# P2P_PROT_1.net
KiCad netlist of a schematic drawn in EAGLE
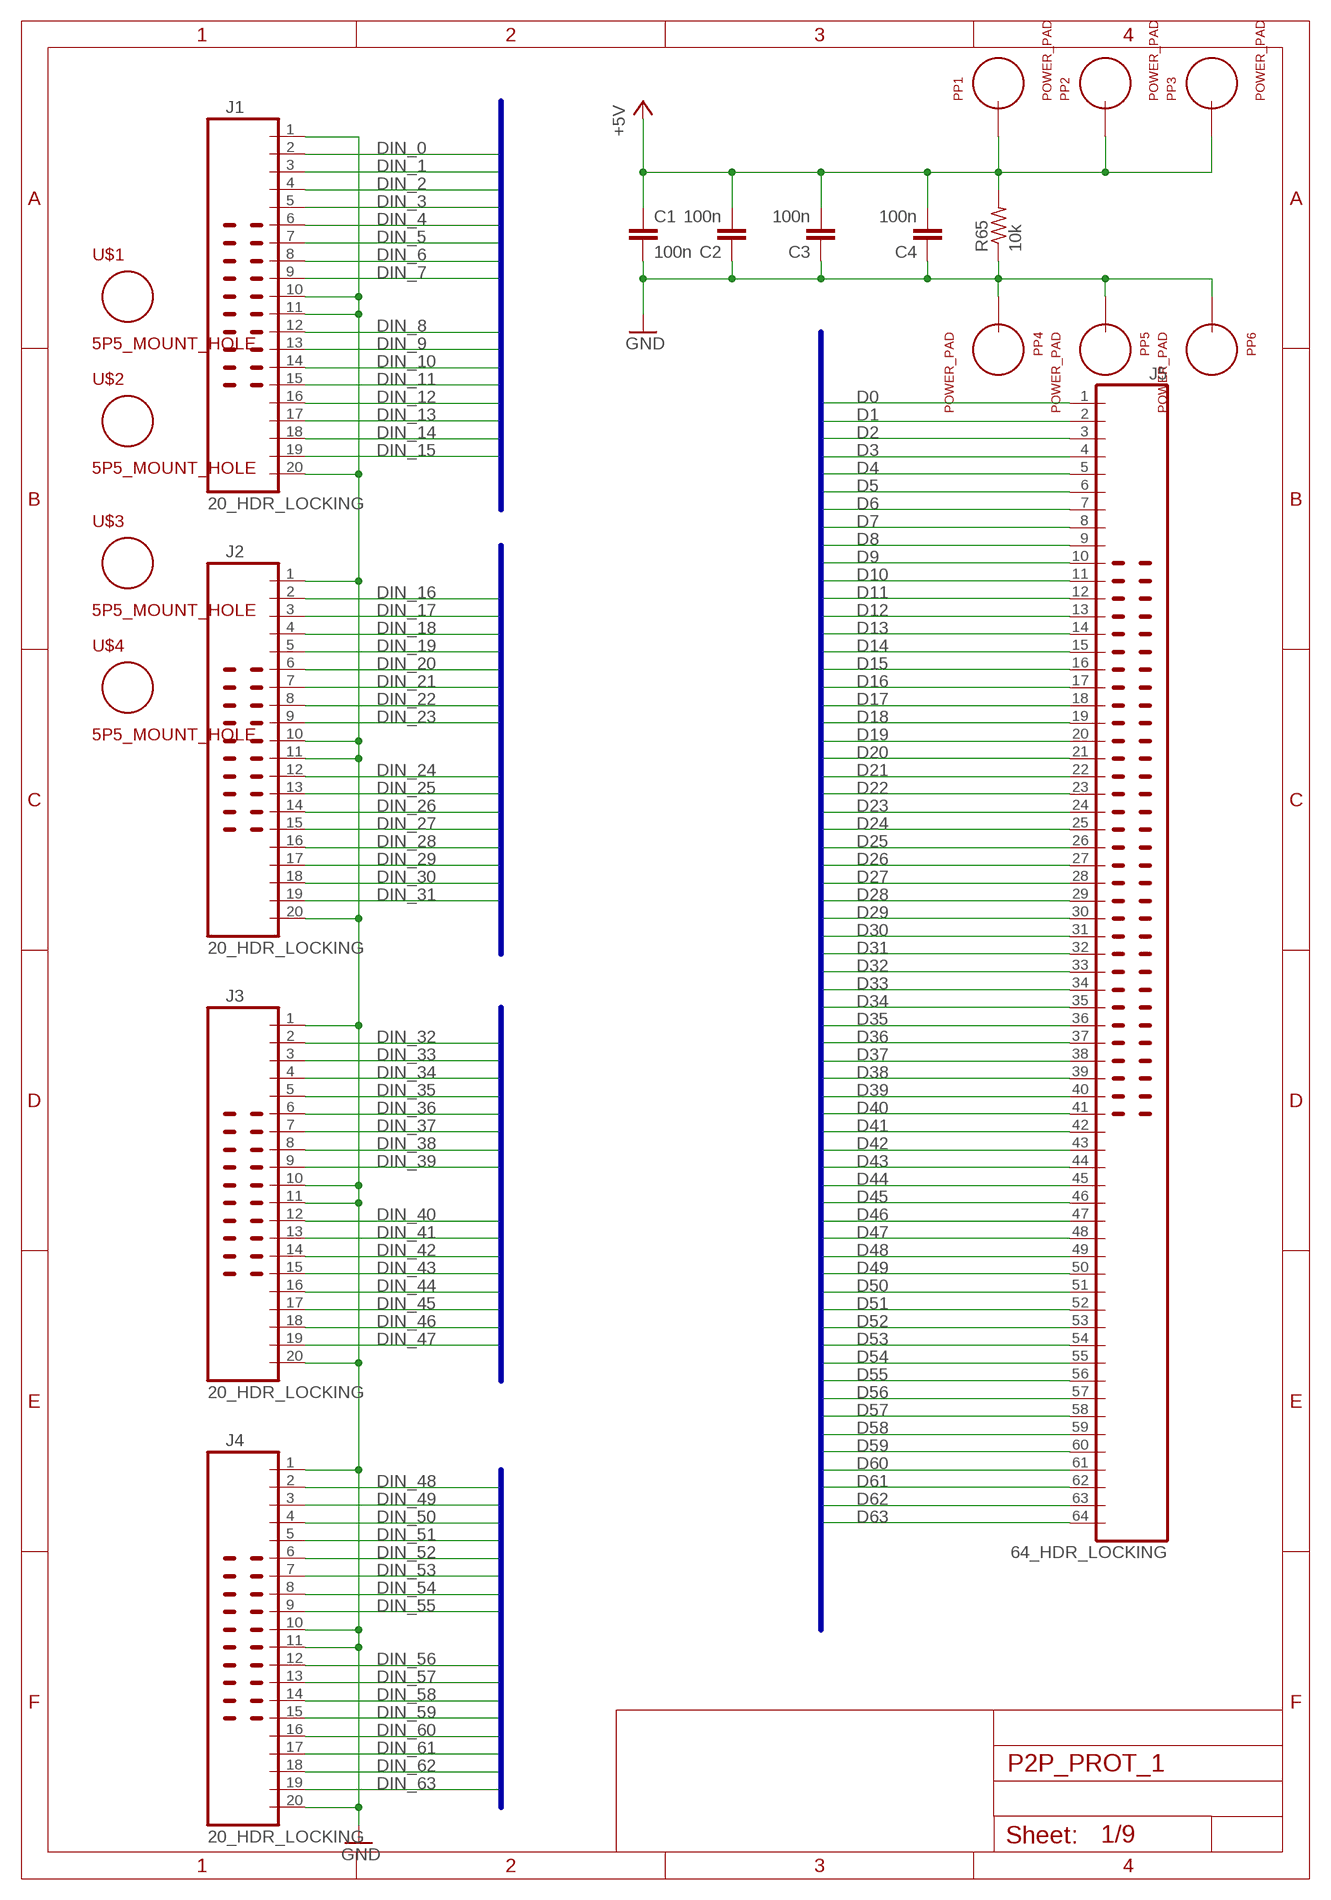
[diagram p0: schematic, sheet 1]
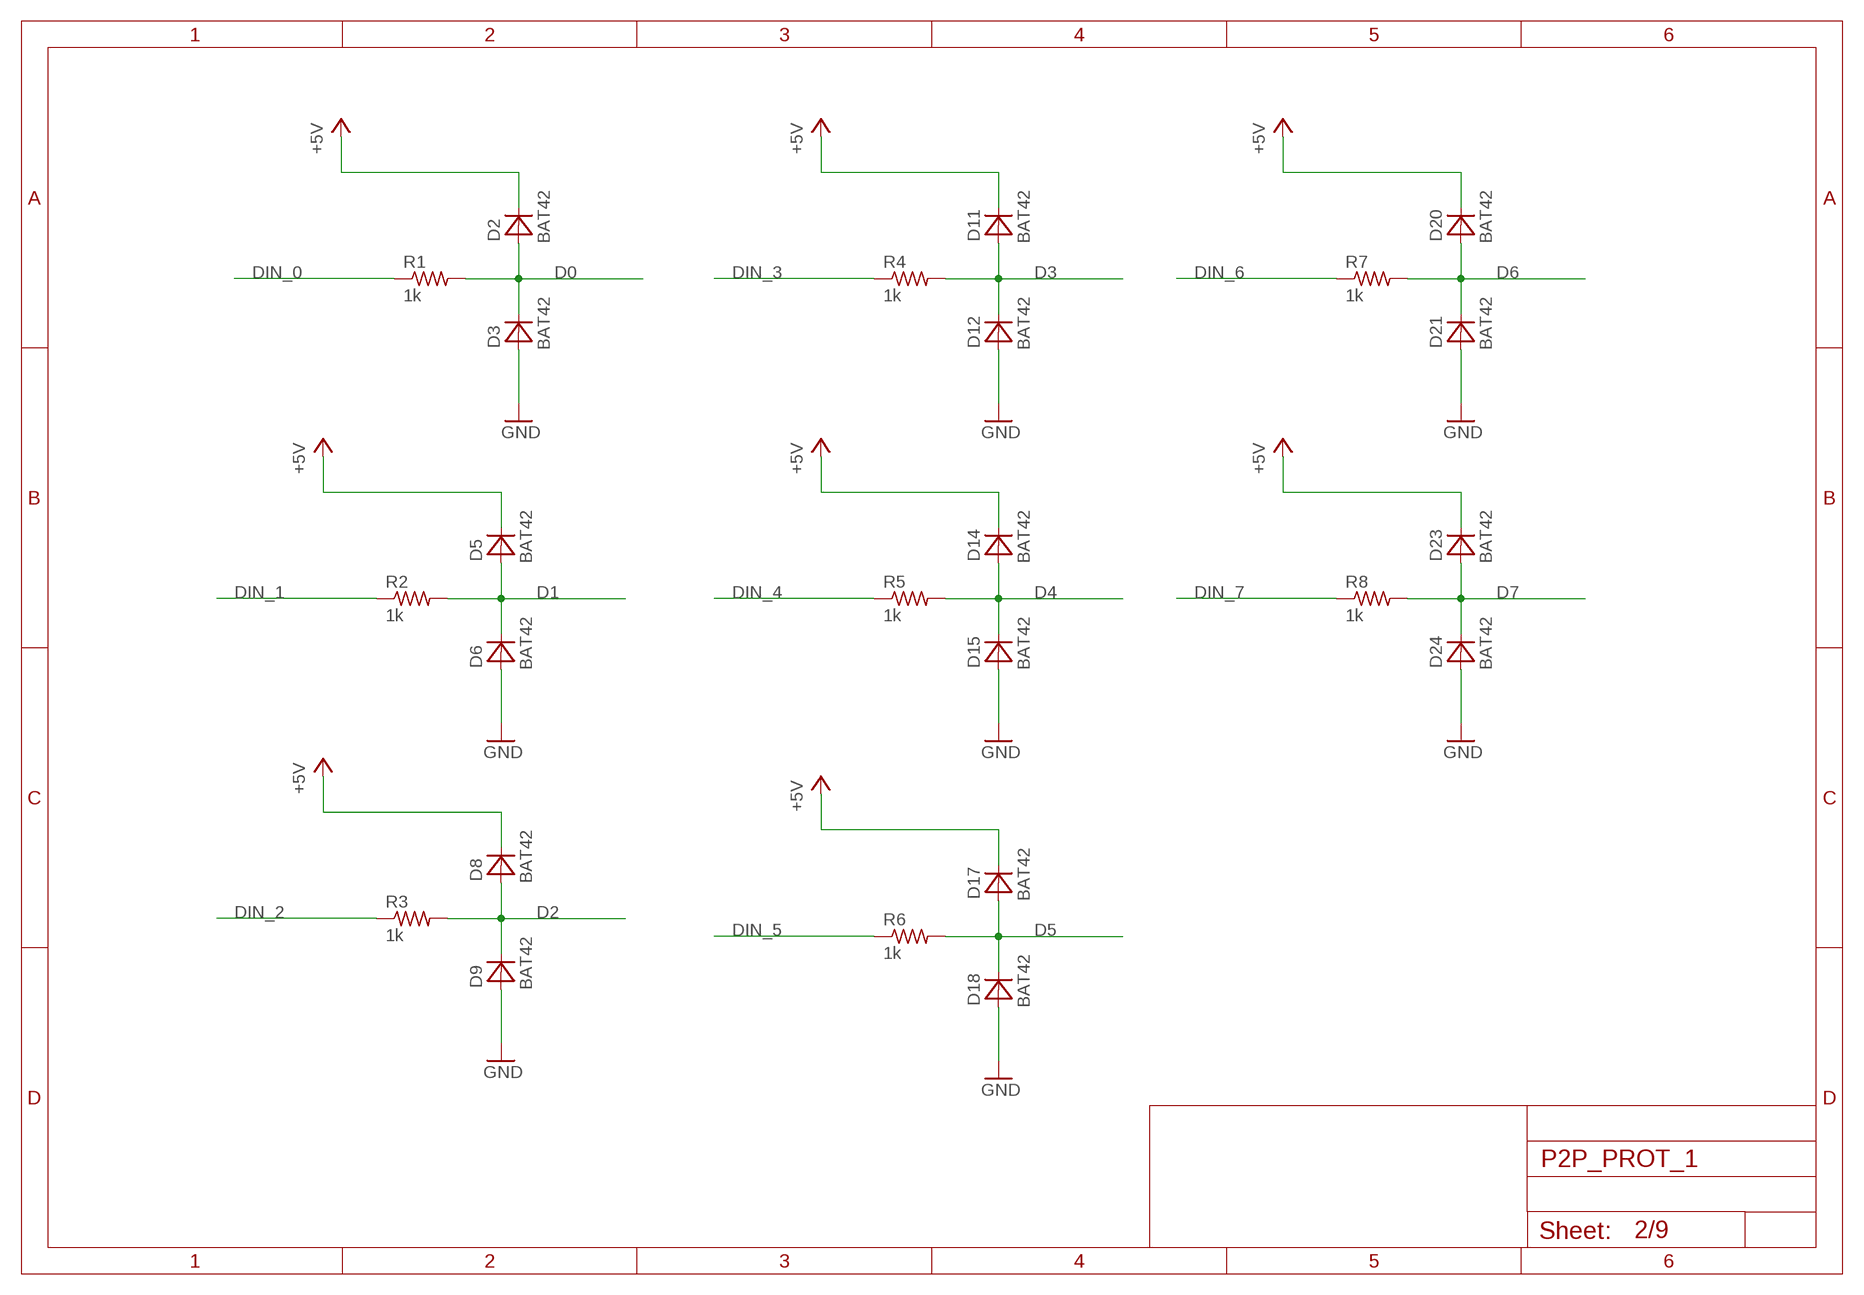
[diagram p1: schematic, sheet 2]
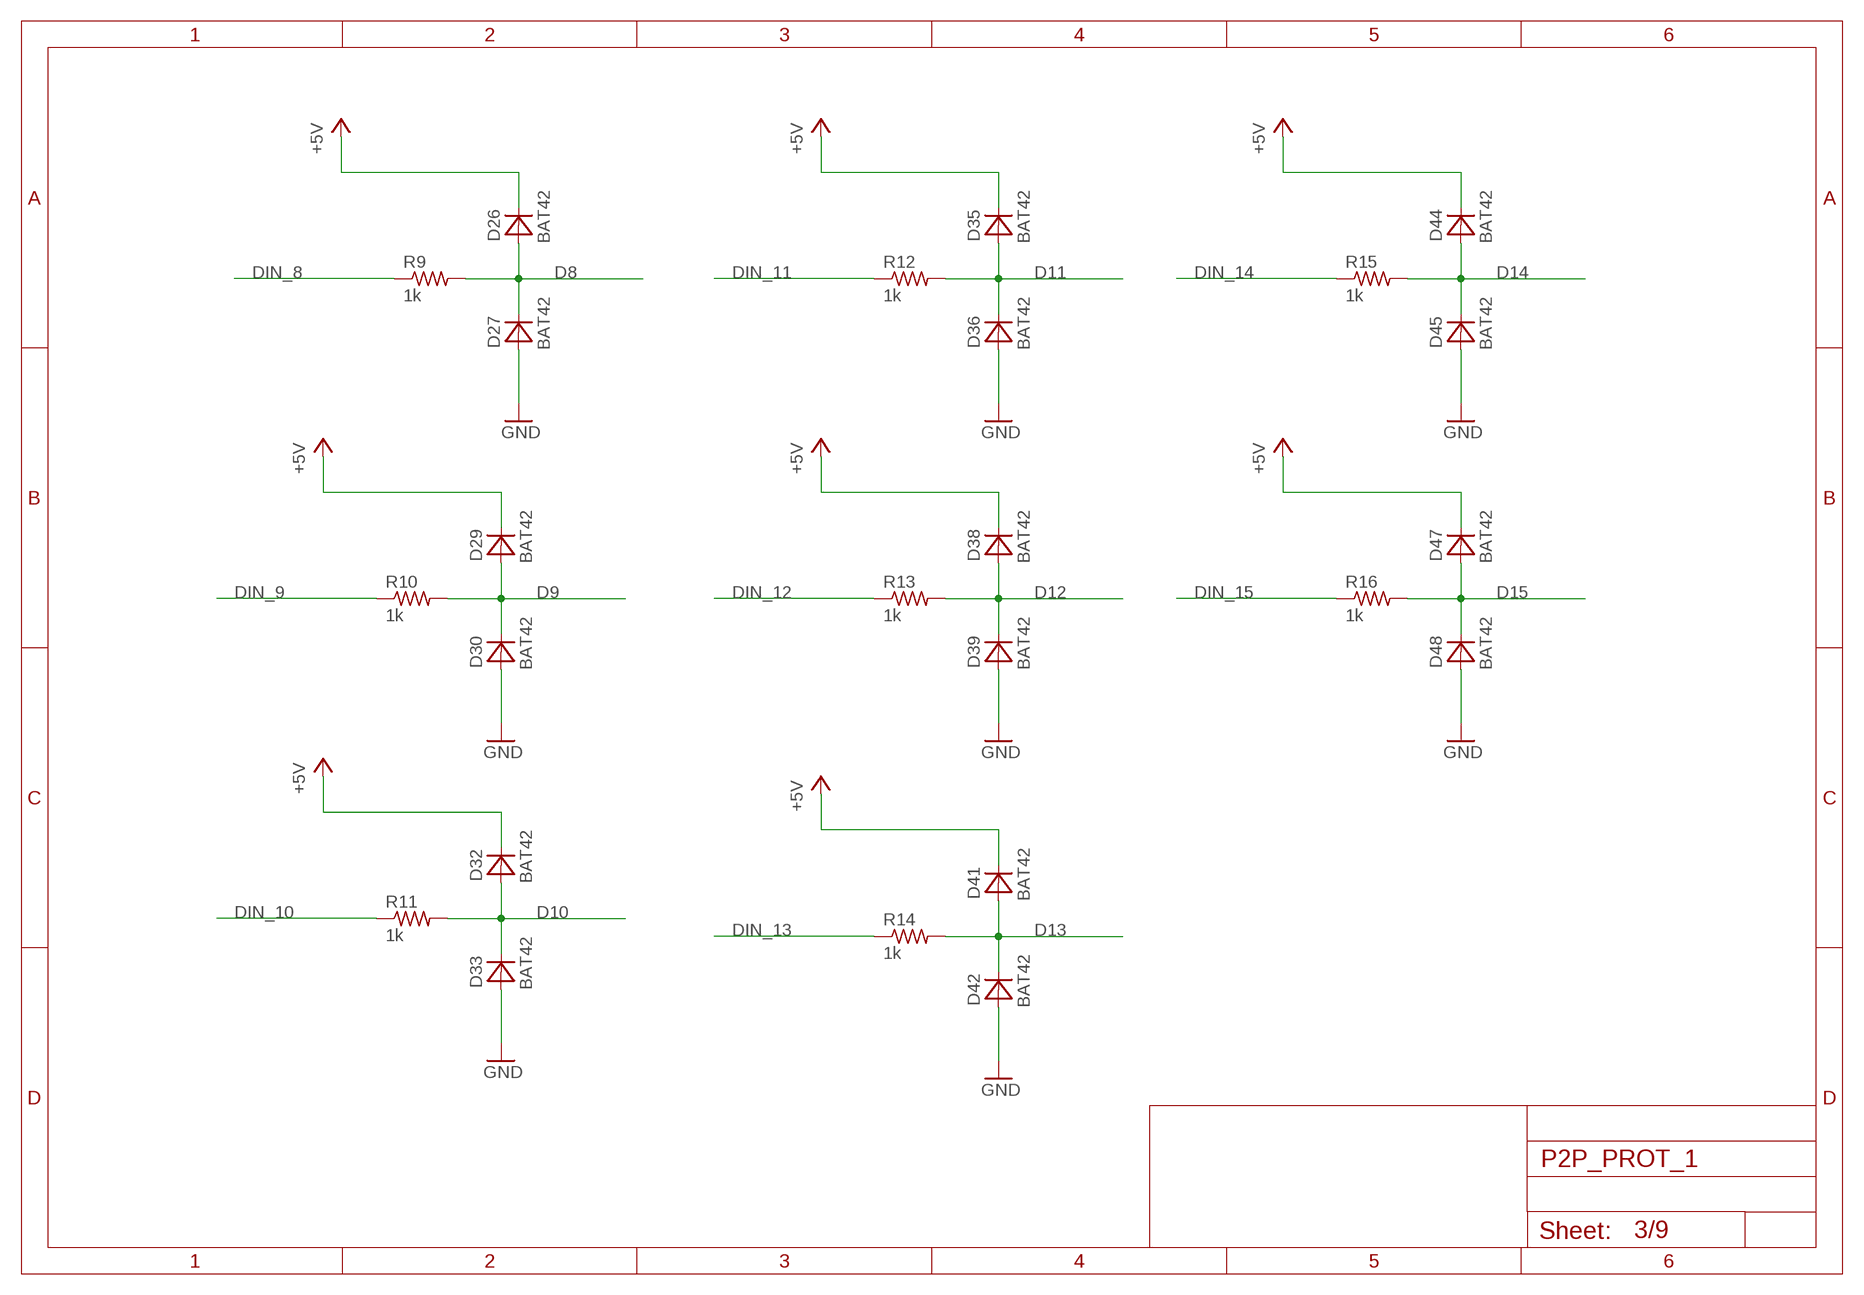
[diagram p2: schematic, sheet 3]
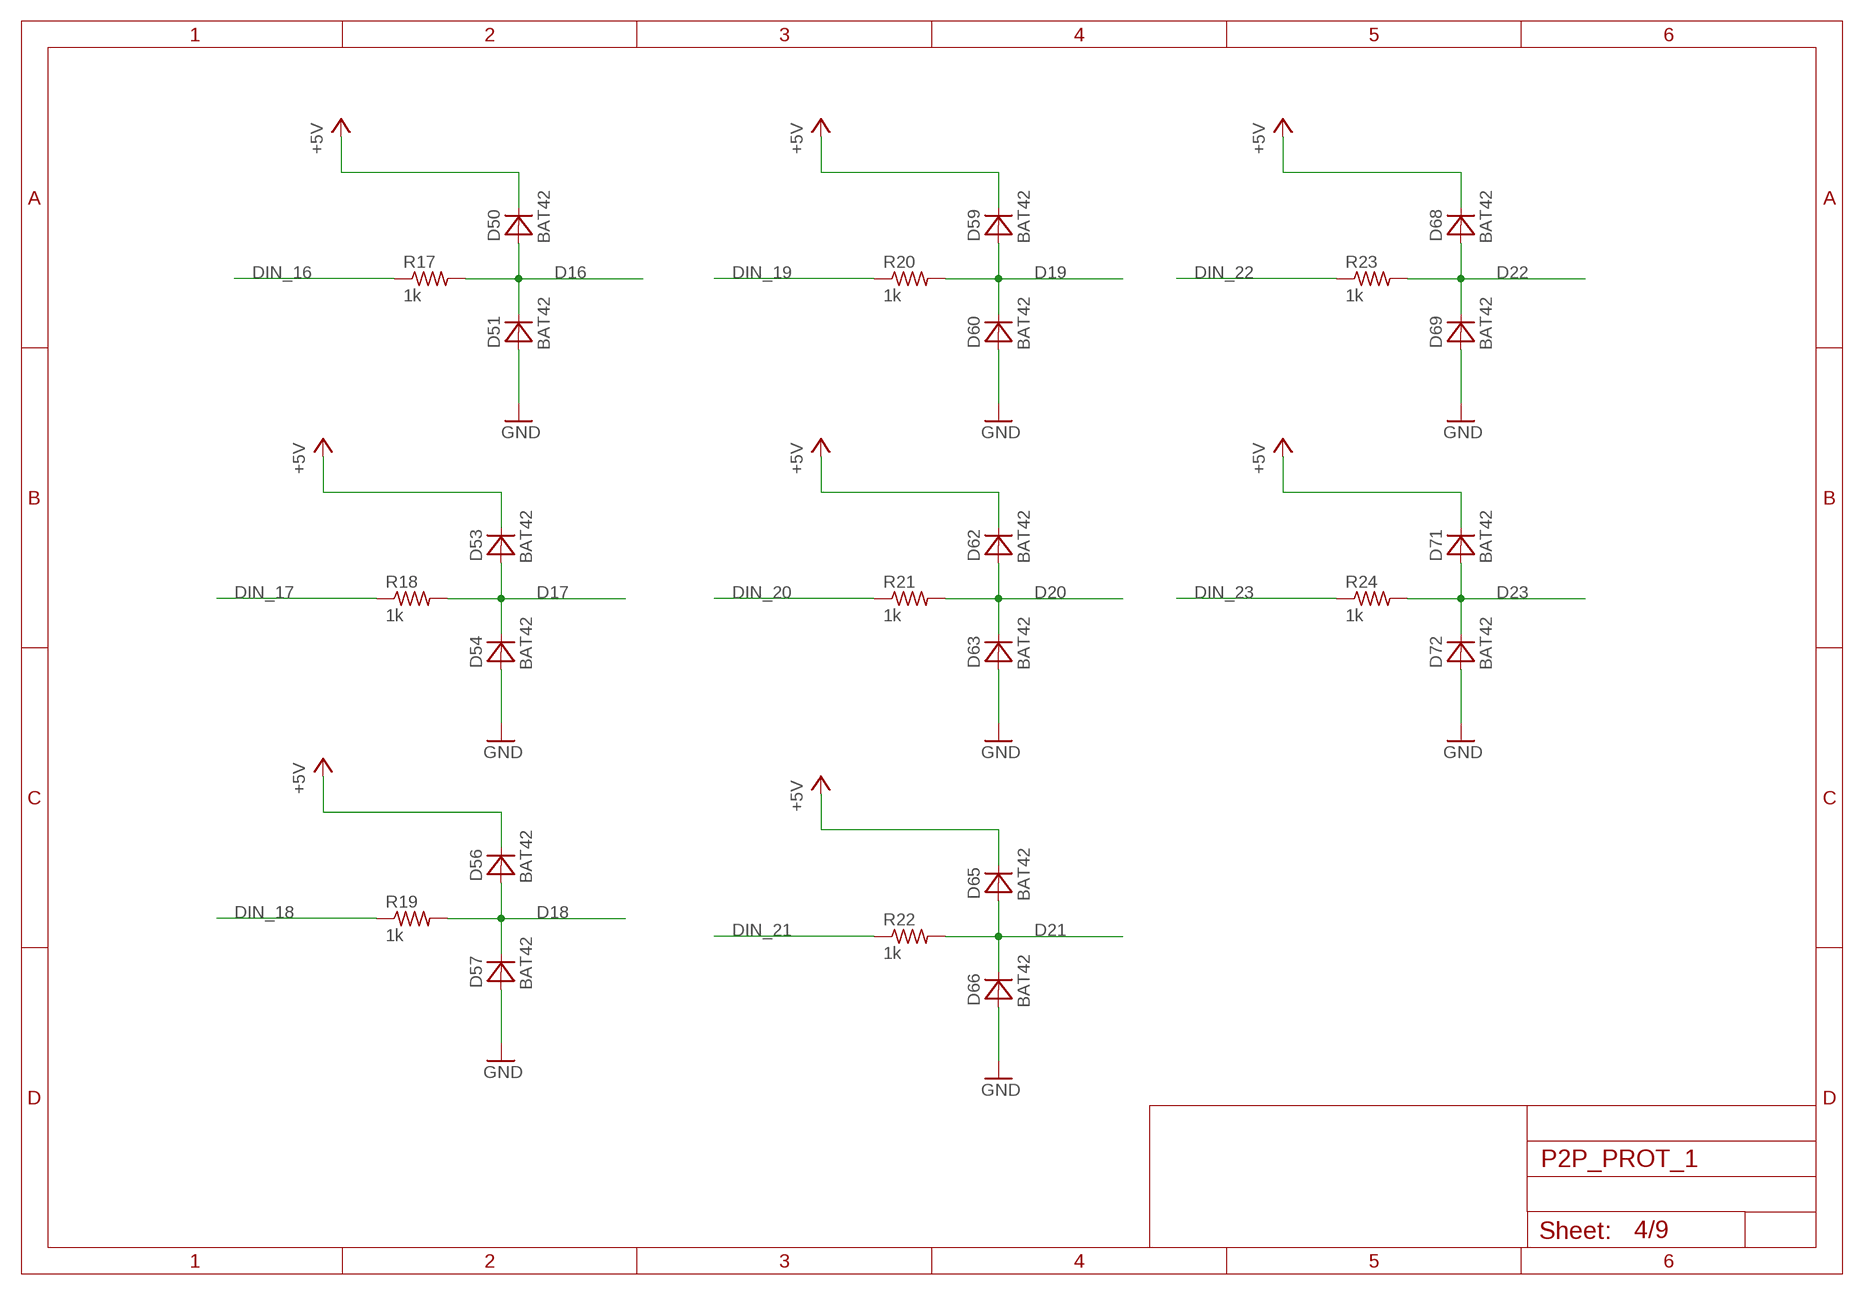
[diagram p3: schematic, sheet 4]
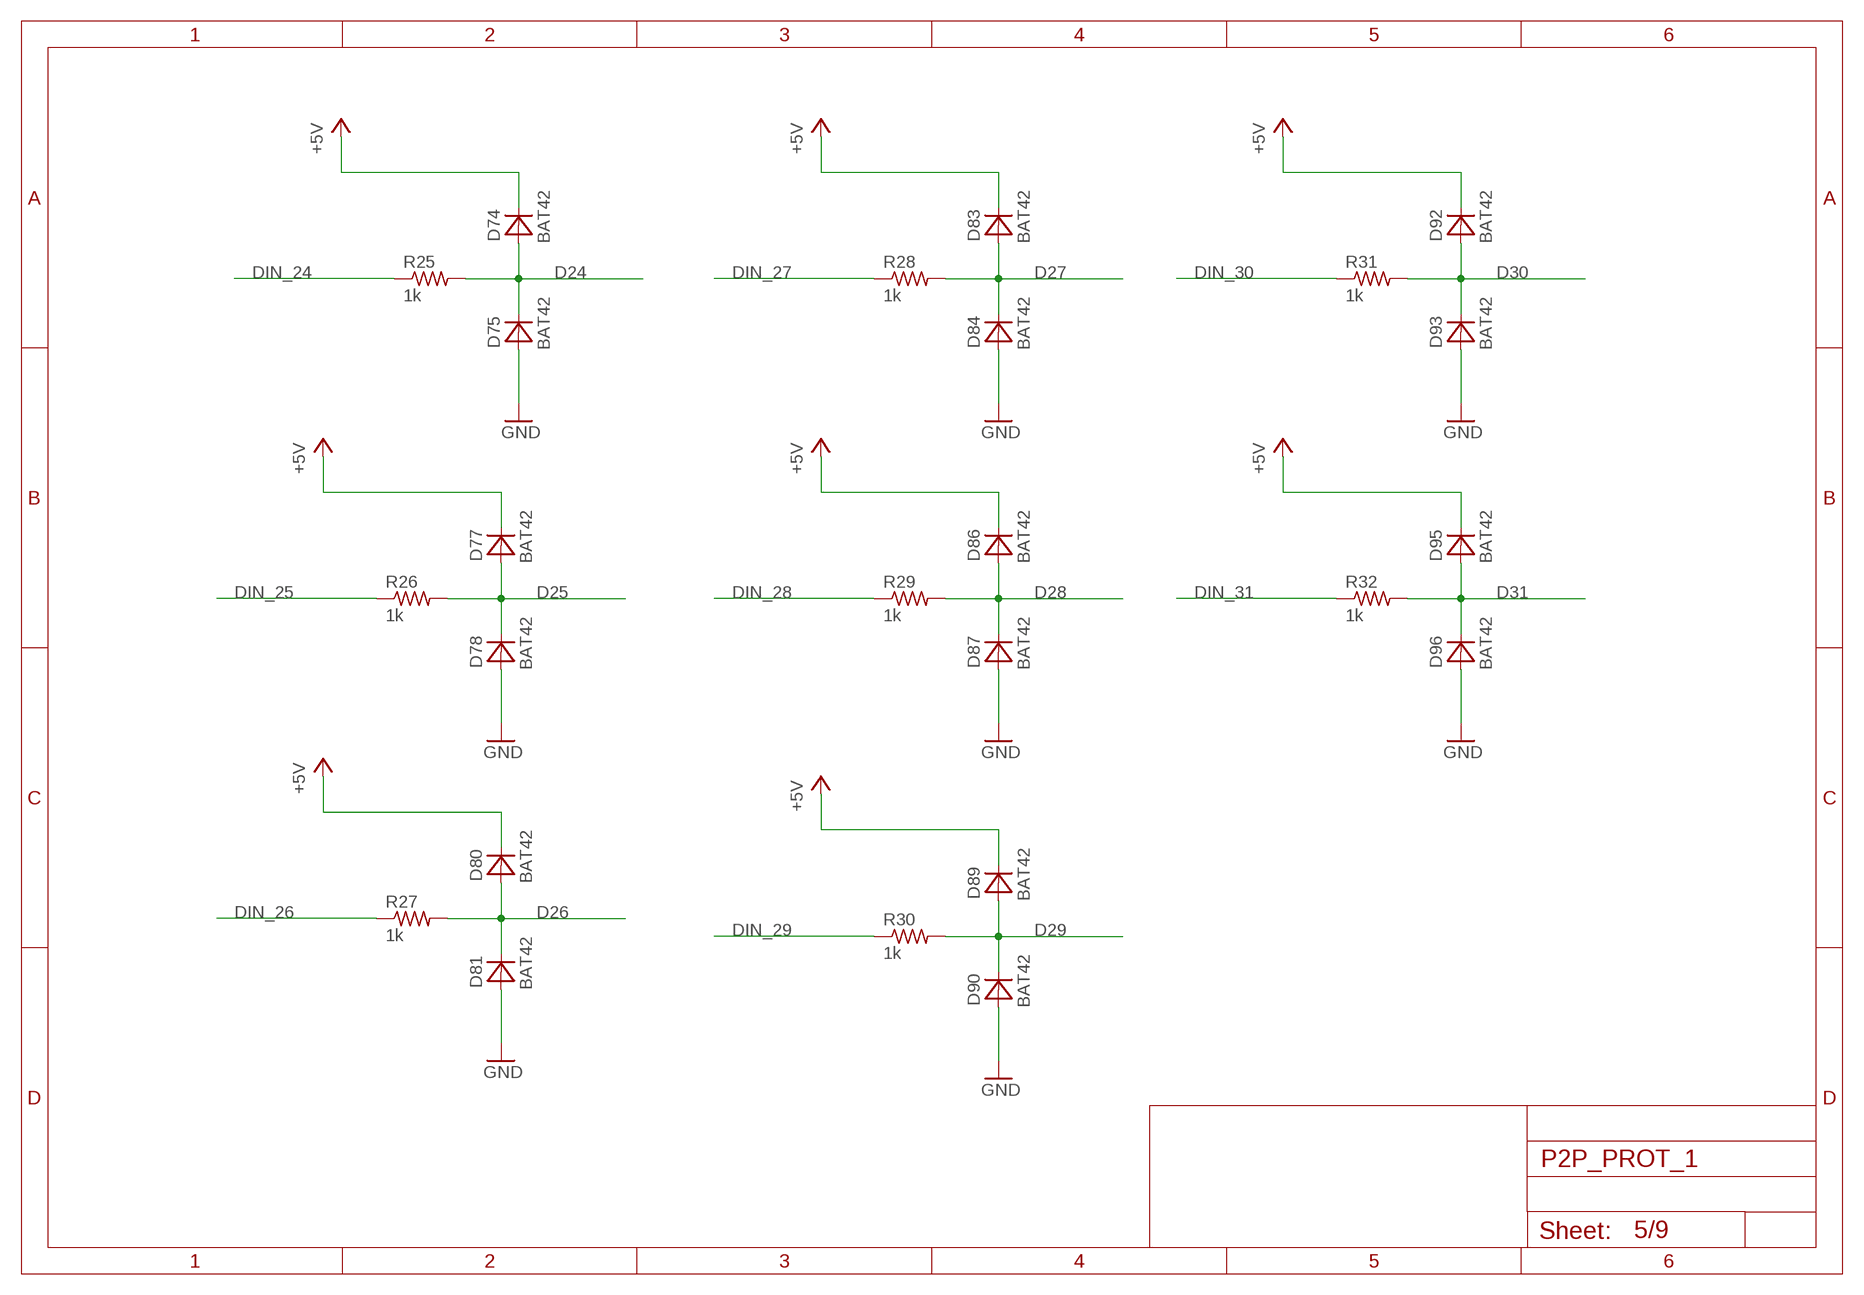
[diagram p4: schematic, sheet 5]
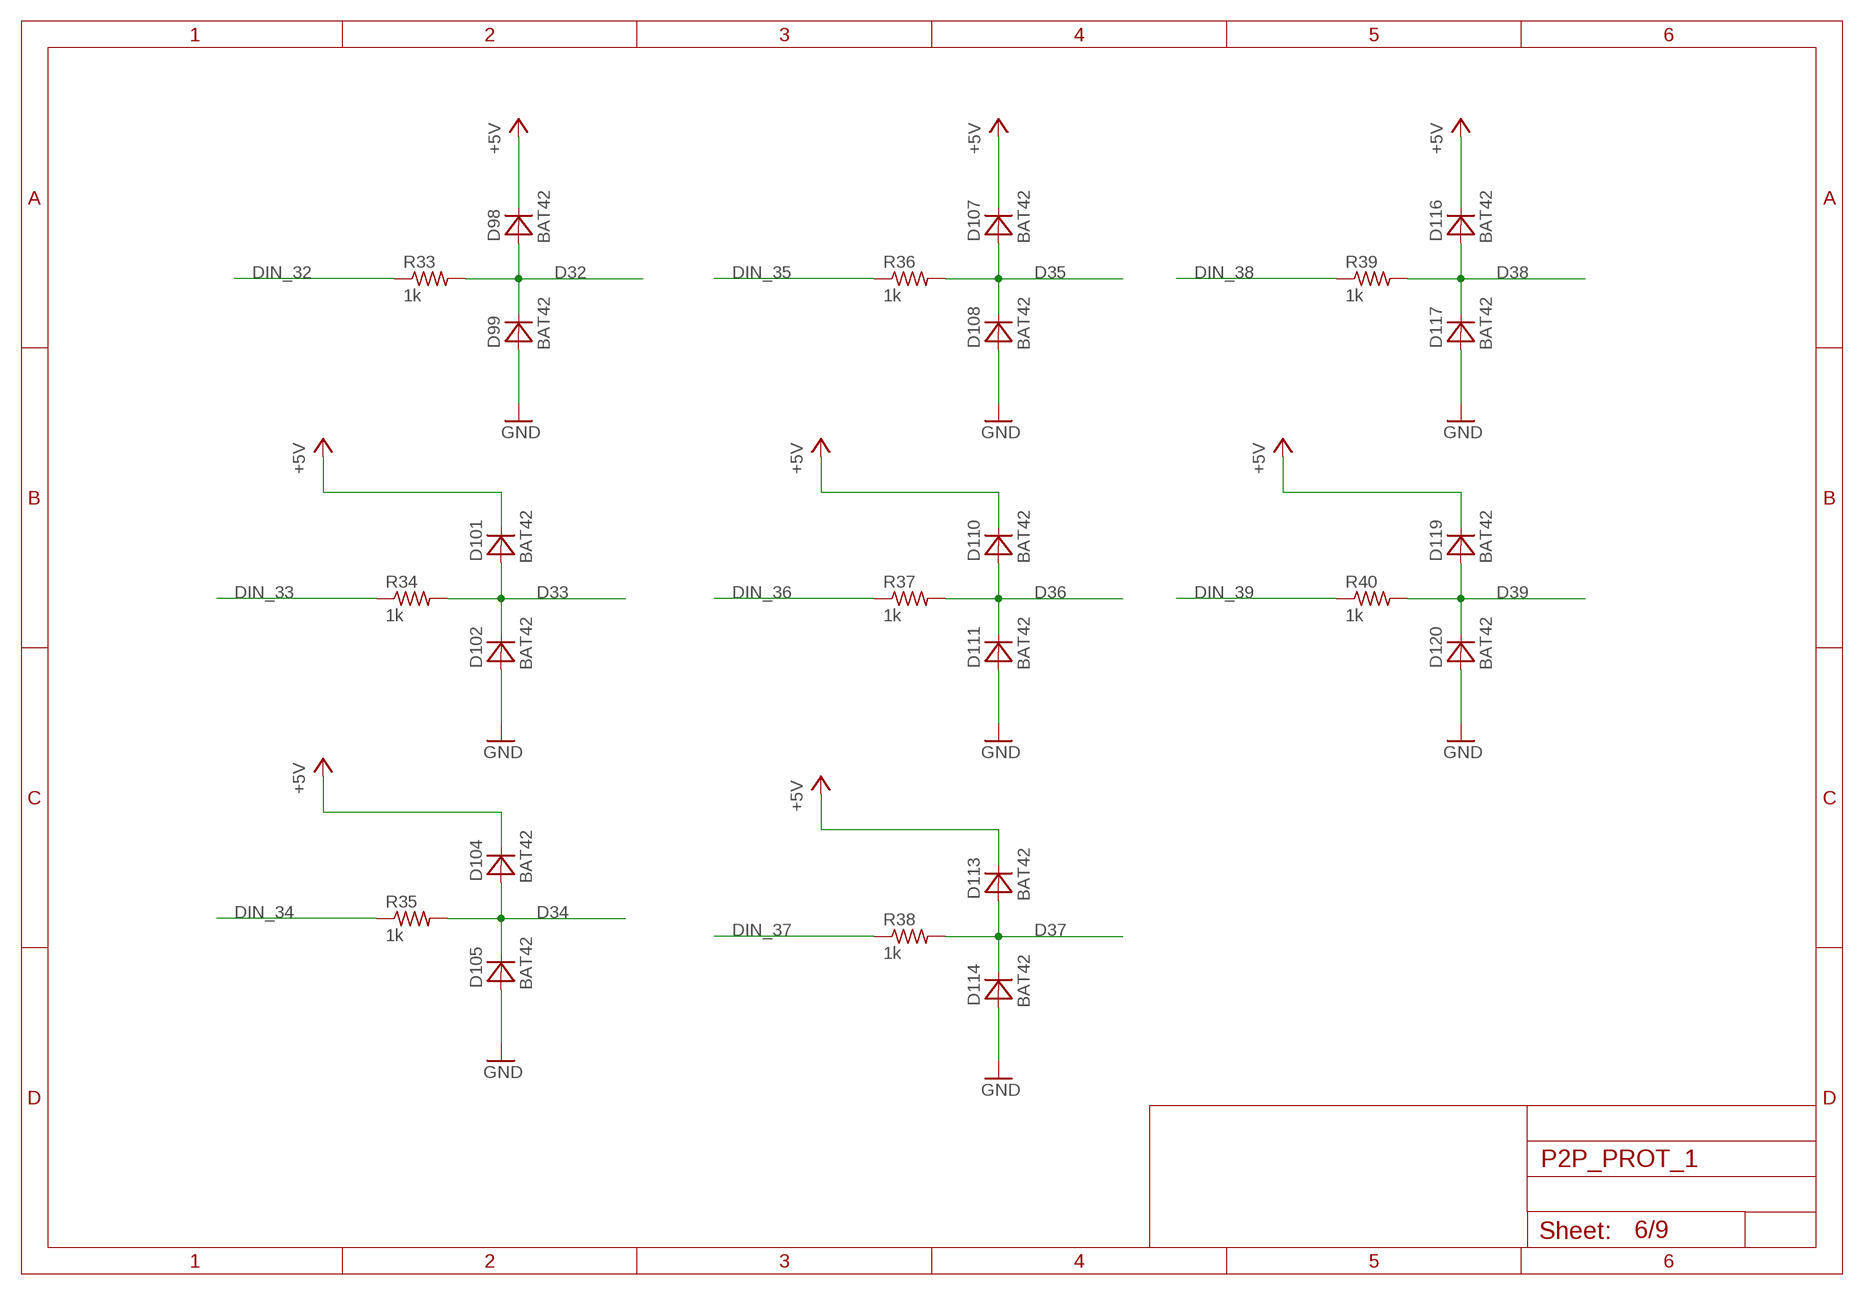
[diagram p5: schematic, sheet 6]
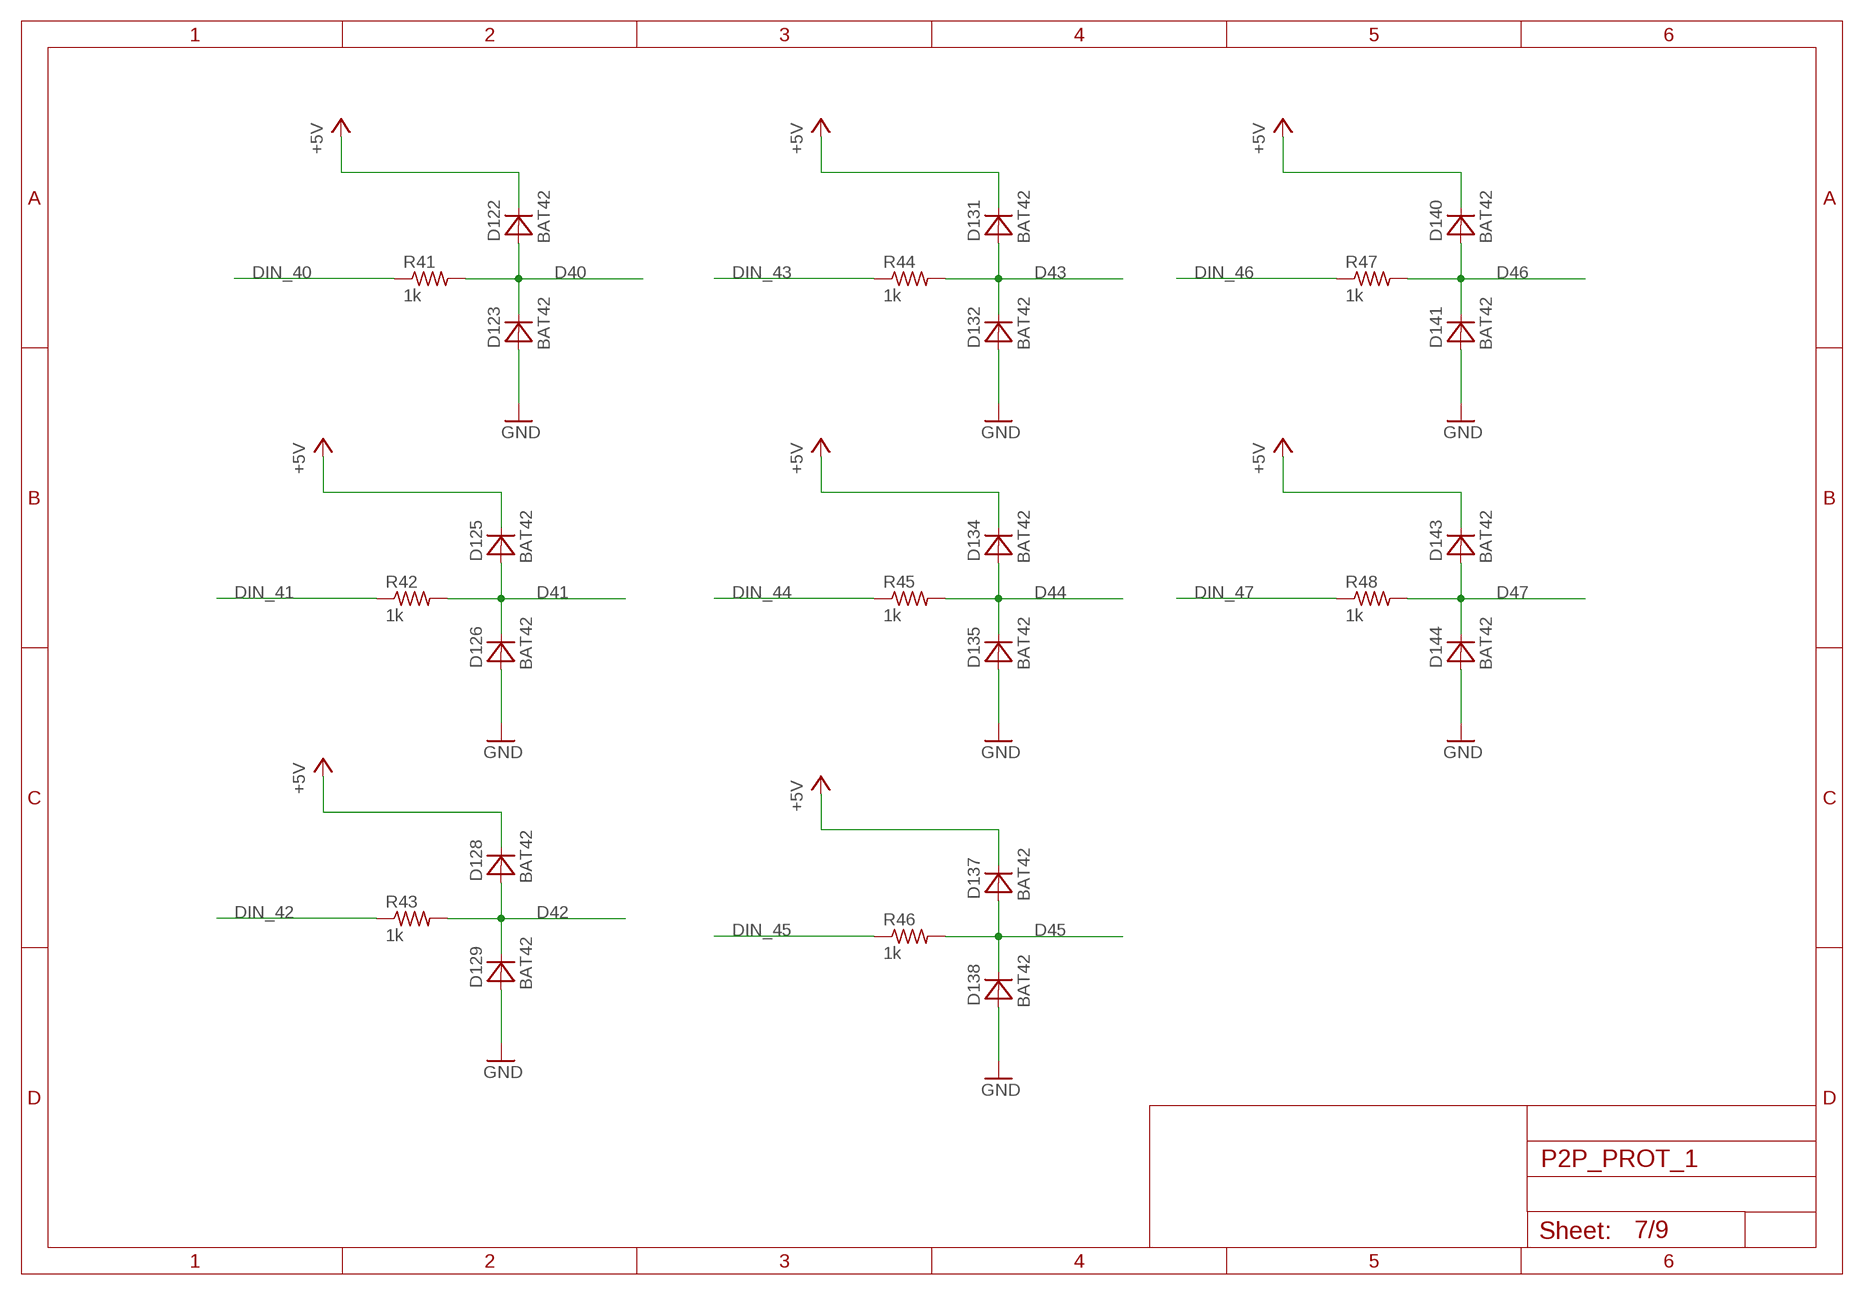
[diagram p6: schematic, sheet 7]
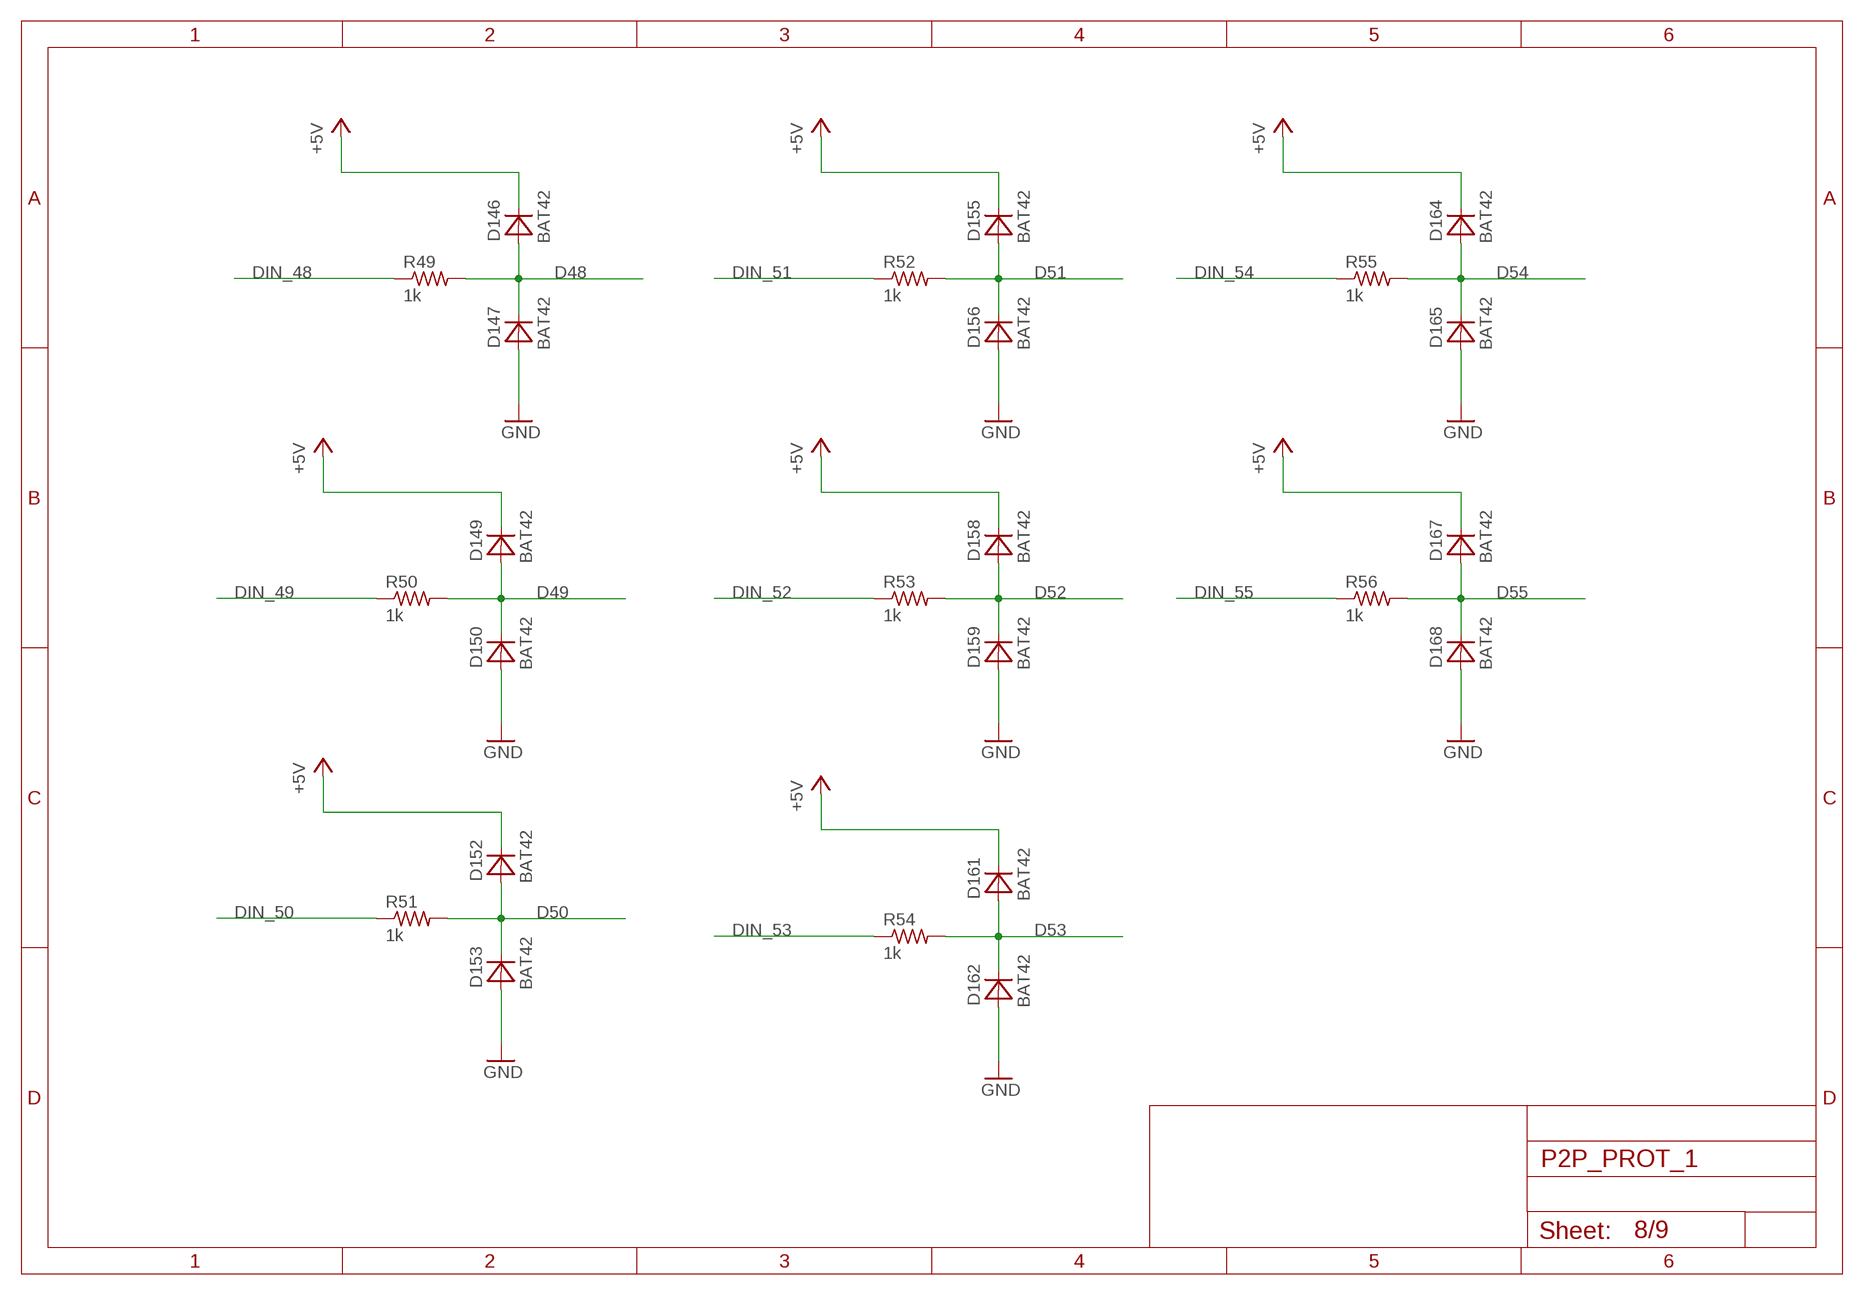
[diagram p7: schematic, sheet 8]
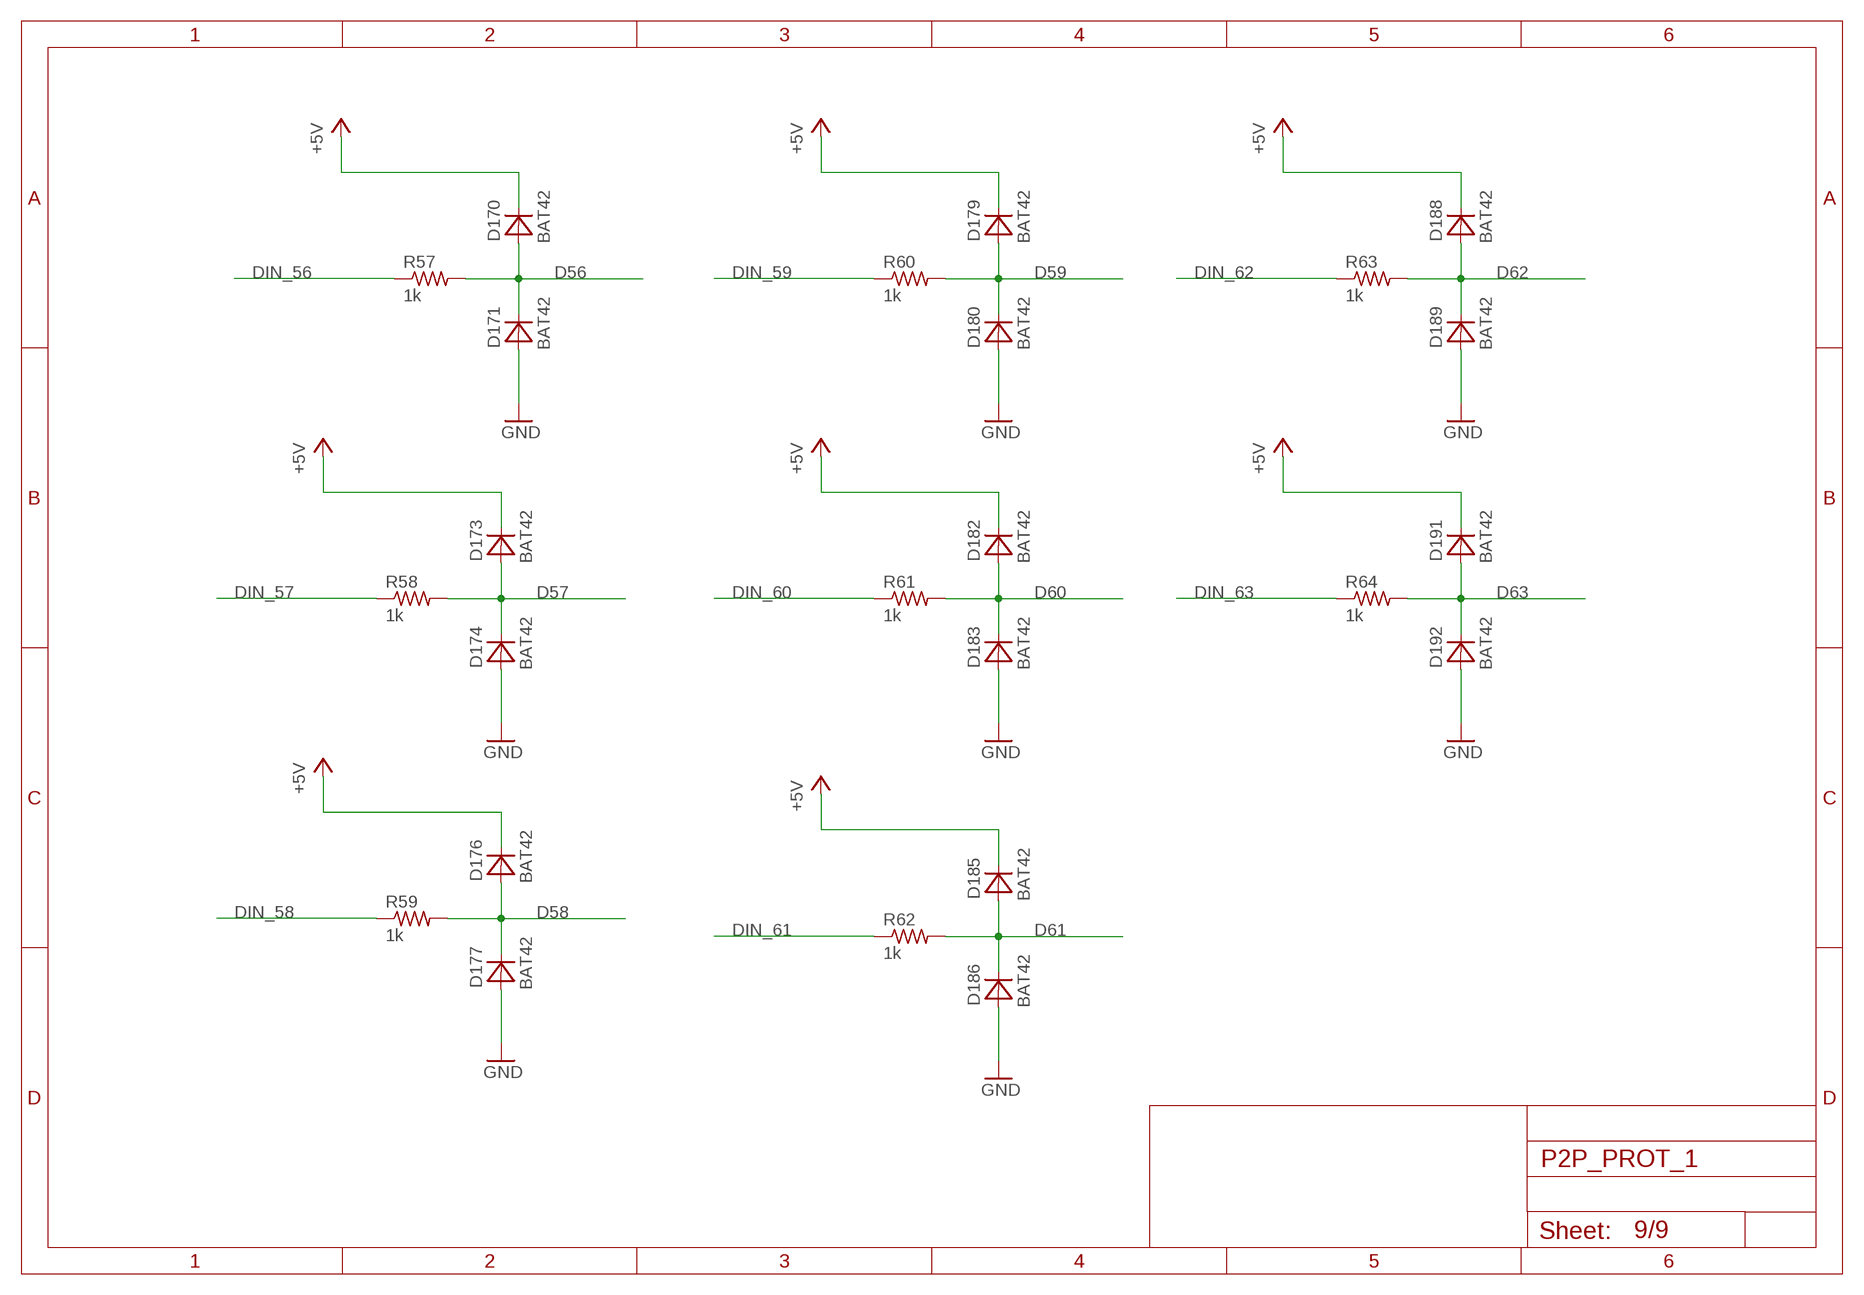
[diagram p8: schematic, sheet 9]

(export (version "E")
  (design (tool "Eeschema 10.0.6"))
  (components
    (comp (ref "C1")
      (value "100n")
      (footprint "eagle-import:CAP_P2INCH")
      (libsource (lib "eagle-import") (part "C_P2INCH"))
    )
    (comp (ref "C2")
      (value "100n")
      (footprint "eagle-import:CAP_P2INCH")
      (libsource (lib "eagle-import") (part "C_P2INCH"))
    )
    (comp (ref "C3")
      (value "100n")
      (footprint "eagle-import:CAP_P2INCH")
      (libsource (lib "eagle-import") (part "C_P2INCH"))
    )
    (comp (ref "C4")
      (value "100n")
      (footprint "eagle-import:CAP_P2INCH")
      (libsource (lib "eagle-import") (part "C_P2INCH"))
    )
    (comp (ref "J1")
      (value "20_HDR_LOCKING")
      (footprint "eagle-import:20_HDR_LOCKING")
      (libsource (lib "eagle-import") (part "20_HDR_LOCKING"))
    )
    (comp (ref "J2")
      (value "20_HDR_LOCKING")
      (footprint "eagle-import:20_HDR_LOCKING")
      (libsource (lib "eagle-import") (part "20_HDR_LOCKING"))
    )
    (comp (ref "J3")
      (value "20_HDR_LOCKING")
      (footprint "eagle-import:20_HDR_LOCKING")
      (libsource (lib "eagle-import") (part "20_HDR_LOCKING"))
    )
    (comp (ref "J4")
      (value "20_HDR_LOCKING")
      (footprint "eagle-import:20_HDR_LOCKING")
      (libsource (lib "eagle-import") (part "20_HDR_LOCKING"))
    )
    (comp (ref "J5")
      (value "64_HDR_LOCKING")
      (footprint "eagle-import:64_HDR_LOCKING")
      (libsource (lib "eagle-import") (part "64_HDR_LOCKING"))
    )
    (comp (ref "PP1")
      (value "POWER_PAD")
      (footprint "eagle-import:POWER_PAD")
      (libsource (lib "eagle-import") (part "POWER_PAD"))
    )
    (comp (ref "PP2")
      (value "POWER_PAD")
      (footprint "eagle-import:POWER_PAD")
      (libsource (lib "eagle-import") (part "POWER_PAD"))
    )
    (comp (ref "PP3")
      (value "POWER_PAD")
      (footprint "eagle-import:POWER_PAD")
      (libsource (lib "eagle-import") (part "POWER_PAD"))
    )
    (comp (ref "PP4")
      (value "POWER_PAD")
      (footprint "eagle-import:POWER_PAD")
      (libsource (lib "eagle-import") (part "POWER_PAD"))
    )
    (comp (ref "PP5")
      (value "POWER_PAD")
      (footprint "eagle-import:POWER_PAD")
      (libsource (lib "eagle-import") (part "POWER_PAD"))
    )
    (comp (ref "PP6")
      (value "POWER_PAD")
      (footprint "eagle-import:POWER_PAD")
      (libsource (lib "eagle-import") (part "POWER_PAD"))
    )
    (comp (ref "R65")
      (value "10k")
      (footprint "eagle-import:R_P2INCH")
      (libsource (lib "eagle-import") (part "R_P2INCH"))
    )
    (comp (ref "U$1")
      (value "5P5_MOUNT_HOLE")
      (footprint "eagle-import:5P5M_HOLE")
      (libsource (lib "eagle-import") (part "5P5_MOUNT_HOLE"))
    )
    (comp (ref "U$2")
      (value "5P5_MOUNT_HOLE")
      (footprint "eagle-import:5P5M_HOLE")
      (libsource (lib "eagle-import") (part "5P5_MOUNT_HOLE"))
    )
    (comp (ref "U$3")
      (value "5P5_MOUNT_HOLE")
      (footprint "eagle-import:5P5M_HOLE")
      (libsource (lib "eagle-import") (part "5P5_MOUNT_HOLE"))
    )
    (comp (ref "U$4")
      (value "5P5_MOUNT_HOLE")
      (footprint "eagle-import:5P5M_HOLE")
      (libsource (lib "eagle-import") (part "5P5_MOUNT_HOLE"))
    )
    (comp (ref "D74")
      (value "BAT42")
      (footprint "eagle-import:DO34-5")
      (libsource (lib "eagle-import") (part "BAT42"))
    )
    (comp (ref "D75")
      (value "BAT42")
      (footprint "eagle-import:DO34-5")
      (libsource (lib "eagle-import") (part "BAT42"))
    )
    (comp (ref "D77")
      (value "BAT42")
      (footprint "eagle-import:DO34-5")
      (libsource (lib "eagle-import") (part "BAT42"))
    )
    (comp (ref "D78")
      (value "BAT42")
      (footprint "eagle-import:DO34-5")
      (libsource (lib "eagle-import") (part "BAT42"))
    )
    (comp (ref "D80")
      (value "BAT42")
      (footprint "eagle-import:DO34-5")
      (libsource (lib "eagle-import") (part "BAT42"))
    )
    (comp (ref "D81")
      (value "BAT42")
      (footprint "eagle-import:DO34-5")
      (libsource (lib "eagle-import") (part "BAT42"))
    )
    (comp (ref "D83")
      (value "BAT42")
      (footprint "eagle-import:DO34-5")
      (libsource (lib "eagle-import") (part "BAT42"))
    )
    (comp (ref "D84")
      (value "BAT42")
      (footprint "eagle-import:DO34-5")
      (libsource (lib "eagle-import") (part "BAT42"))
    )
    (comp (ref "D86")
      (value "BAT42")
      (footprint "eagle-import:DO34-5")
      (libsource (lib "eagle-import") (part "BAT42"))
    )
    (comp (ref "D87")
      (value "BAT42")
      (footprint "eagle-import:DO34-5")
      (libsource (lib "eagle-import") (part "BAT42"))
    )
    (comp (ref "D89")
      (value "BAT42")
      (footprint "eagle-import:DO34-5")
      (libsource (lib "eagle-import") (part "BAT42"))
    )
    (comp (ref "D90")
      (value "BAT42")
      (footprint "eagle-import:DO34-5")
      (libsource (lib "eagle-import") (part "BAT42"))
    )
    (comp (ref "D92")
      (value "BAT42")
      (footprint "eagle-import:DO34-5")
      (libsource (lib "eagle-import") (part "BAT42"))
    )
    (comp (ref "D93")
      (value "BAT42")
      (footprint "eagle-import:DO34-5")
      (libsource (lib "eagle-import") (part "BAT42"))
    )
    (comp (ref "D95")
      (value "BAT42")
      (footprint "eagle-import:DO34-5")
      (libsource (lib "eagle-import") (part "BAT42"))
    )
    (comp (ref "D96")
      (value "BAT42")
      (footprint "eagle-import:DO34-5")
      (libsource (lib "eagle-import") (part "BAT42"))
    )
    (comp (ref "R25")
      (value "1k")
      (footprint "eagle-import:R_P2INCH")
      (libsource (lib "eagle-import") (part "R_P2INCH"))
    )
    (comp (ref "R26")
      (value "1k")
      (footprint "eagle-import:R_P2INCH")
      (libsource (lib "eagle-import") (part "R_P2INCH"))
    )
    (comp (ref "R27")
      (value "1k")
      (footprint "eagle-import:R_P2INCH")
      (libsource (lib "eagle-import") (part "R_P2INCH"))
    )
    (comp (ref "R28")
      (value "1k")
      (footprint "eagle-import:R_P2INCH")
      (libsource (lib "eagle-import") (part "R_P2INCH"))
    )
    (comp (ref "R29")
      (value "1k")
      (footprint "eagle-import:R_P2INCH")
      (libsource (lib "eagle-import") (part "R_P2INCH"))
    )
    (comp (ref "R30")
      (value "1k")
      (footprint "eagle-import:R_P2INCH")
      (libsource (lib "eagle-import") (part "R_P2INCH"))
    )
    (comp (ref "R31")
      (value "1k")
      (footprint "eagle-import:R_P2INCH")
      (libsource (lib "eagle-import") (part "R_P2INCH"))
    )
    (comp (ref "R32")
      (value "1k")
      (footprint "eagle-import:R_P2INCH")
      (libsource (lib "eagle-import") (part "R_P2INCH"))
    )
    (comp (ref "D170")
      (value "BAT42")
      (footprint "eagle-import:DO34-5")
      (libsource (lib "eagle-import") (part "BAT42"))
    )
    (comp (ref "D171")
      (value "BAT42")
      (footprint "eagle-import:DO34-5")
      (libsource (lib "eagle-import") (part "BAT42"))
    )
    (comp (ref "D173")
      (value "BAT42")
      (footprint "eagle-import:DO34-5")
      (libsource (lib "eagle-import") (part "BAT42"))
    )
    (comp (ref "D174")
      (value "BAT42")
      (footprint "eagle-import:DO34-5")
      (libsource (lib "eagle-import") (part "BAT42"))
    )
    (comp (ref "D176")
      (value "BAT42")
      (footprint "eagle-import:DO34-5")
      (libsource (lib "eagle-import") (part "BAT42"))
    )
    (comp (ref "D177")
      (value "BAT42")
      (footprint "eagle-import:DO34-5")
      (libsource (lib "eagle-import") (part "BAT42"))
    )
    (comp (ref "D179")
      (value "BAT42")
      (footprint "eagle-import:DO34-5")
      (libsource (lib "eagle-import") (part "BAT42"))
    )
    (comp (ref "D180")
      (value "BAT42")
      (footprint "eagle-import:DO34-5")
      (libsource (lib "eagle-import") (part "BAT42"))
    )
    (comp (ref "D182")
      (value "BAT42")
      (footprint "eagle-import:DO34-5")
      (libsource (lib "eagle-import") (part "BAT42"))
    )
    (comp (ref "D183")
      (value "BAT42")
      (footprint "eagle-import:DO34-5")
      (libsource (lib "eagle-import") (part "BAT42"))
    )
    (comp (ref "D185")
      (value "BAT42")
      (footprint "eagle-import:DO34-5")
      (libsource (lib "eagle-import") (part "BAT42"))
    )
    (comp (ref "D186")
      (value "BAT42")
      (footprint "eagle-import:DO34-5")
      (libsource (lib "eagle-import") (part "BAT42"))
    )
    (comp (ref "D188")
      (value "BAT42")
      (footprint "eagle-import:DO34-5")
      (libsource (lib "eagle-import") (part "BAT42"))
    )
    (comp (ref "D189")
      (value "BAT42")
      (footprint "eagle-import:DO34-5")
      (libsource (lib "eagle-import") (part "BAT42"))
    )
    (comp (ref "D191")
      (value "BAT42")
      (footprint "eagle-import:DO34-5")
      (libsource (lib "eagle-import") (part "BAT42"))
    )
    (comp (ref "D192")
      (value "BAT42")
      (footprint "eagle-import:DO34-5")
      (libsource (lib "eagle-import") (part "BAT42"))
    )
    (comp (ref "R57")
      (value "1k")
      (footprint "eagle-import:R_P2INCH")
      (libsource (lib "eagle-import") (part "R_P2INCH"))
    )
    (comp (ref "R58")
      (value "1k")
      (footprint "eagle-import:R_P2INCH")
      (libsource (lib "eagle-import") (part "R_P2INCH"))
    )
    (comp (ref "R59")
      (value "1k")
      (footprint "eagle-import:R_P2INCH")
      (libsource (lib "eagle-import") (part "R_P2INCH"))
    )
    (comp (ref "R60")
      (value "1k")
      (footprint "eagle-import:R_P2INCH")
      (libsource (lib "eagle-import") (part "R_P2INCH"))
    )
    (comp (ref "R61")
      (value "1k")
      (footprint "eagle-import:R_P2INCH")
      (libsource (lib "eagle-import") (part "R_P2INCH"))
    )
    (comp (ref "R62")
      (value "1k")
      (footprint "eagle-import:R_P2INCH")
      (libsource (lib "eagle-import") (part "R_P2INCH"))
    )
    (comp (ref "R63")
      (value "1k")
      (footprint "eagle-import:R_P2INCH")
      (libsource (lib "eagle-import") (part "R_P2INCH"))
    )
    (comp (ref "R64")
      (value "1k")
      (footprint "eagle-import:R_P2INCH")
      (libsource (lib "eagle-import") (part "R_P2INCH"))
    )
    (comp (ref "D26")
      (value "BAT42")
      (footprint "eagle-import:DO34-5")
      (libsource (lib "eagle-import") (part "BAT42"))
    )
    (comp (ref "D27")
      (value "BAT42")
      (footprint "eagle-import:DO34-5")
      (libsource (lib "eagle-import") (part "BAT42"))
    )
    (comp (ref "D29")
      (value "BAT42")
      (footprint "eagle-import:DO34-5")
      (libsource (lib "eagle-import") (part "BAT42"))
    )
    (comp (ref "D30")
      (value "BAT42")
      (footprint "eagle-import:DO34-5")
      (libsource (lib "eagle-import") (part "BAT42"))
    )
    (comp (ref "D32")
      (value "BAT42")
      (footprint "eagle-import:DO34-5")
      (libsource (lib "eagle-import") (part "BAT42"))
    )
    (comp (ref "D33")
      (value "BAT42")
      (footprint "eagle-import:DO34-5")
      (libsource (lib "eagle-import") (part "BAT42"))
    )
    (comp (ref "D35")
      (value "BAT42")
      (footprint "eagle-import:DO34-5")
      (libsource (lib "eagle-import") (part "BAT42"))
    )
    (comp (ref "D36")
      (value "BAT42")
      (footprint "eagle-import:DO34-5")
      (libsource (lib "eagle-import") (part "BAT42"))
    )
    (comp (ref "D38")
      (value "BAT42")
      (footprint "eagle-import:DO34-5")
      (libsource (lib "eagle-import") (part "BAT42"))
    )
    (comp (ref "D39")
      (value "BAT42")
      (footprint "eagle-import:DO34-5")
      (libsource (lib "eagle-import") (part "BAT42"))
    )
    (comp (ref "D41")
      (value "BAT42")
      (footprint "eagle-import:DO34-5")
      (libsource (lib "eagle-import") (part "BAT42"))
    )
    (comp (ref "D42")
      (value "BAT42")
      (footprint "eagle-import:DO34-5")
      (libsource (lib "eagle-import") (part "BAT42"))
    )
    (comp (ref "D44")
      (value "BAT42")
      (footprint "eagle-import:DO34-5")
      (libsource (lib "eagle-import") (part "BAT42"))
    )
    (comp (ref "D45")
      (value "BAT42")
      (footprint "eagle-import:DO34-5")
      (libsource (lib "eagle-import") (part "BAT42"))
    )
    (comp (ref "D47")
      (value "BAT42")
      (footprint "eagle-import:DO34-5")
      (libsource (lib "eagle-import") (part "BAT42"))
    )
    (comp (ref "D48")
      (value "BAT42")
      (footprint "eagle-import:DO34-5")
      (libsource (lib "eagle-import") (part "BAT42"))
    )
    (comp (ref "R9")
      (value "1k")
      (footprint "eagle-import:R_P2INCH")
      (libsource (lib "eagle-import") (part "R_P2INCH"))
    )
    (comp (ref "R10")
      (value "1k")
      (footprint "eagle-import:R_P2INCH")
      (libsource (lib "eagle-import") (part "R_P2INCH"))
    )
    (comp (ref "R11")
      (value "1k")
      (footprint "eagle-import:R_P2INCH")
      (libsource (lib "eagle-import") (part "R_P2INCH"))
    )
    (comp (ref "R12")
      (value "1k")
      (footprint "eagle-import:R_P2INCH")
      (libsource (lib "eagle-import") (part "R_P2INCH"))
    )
    (comp (ref "R13")
      (value "1k")
      (footprint "eagle-import:R_P2INCH")
      (libsource (lib "eagle-import") (part "R_P2INCH"))
    )
    (comp (ref "R14")
      (value "1k")
      (footprint "eagle-import:R_P2INCH")
      (libsource (lib "eagle-import") (part "R_P2INCH"))
    )
    (comp (ref "R15")
      (value "1k")
      (footprint "eagle-import:R_P2INCH")
      (libsource (lib "eagle-import") (part "R_P2INCH"))
    )
    (comp (ref "R16")
      (value "1k")
      (footprint "eagle-import:R_P2INCH")
      (libsource (lib "eagle-import") (part "R_P2INCH"))
    )
    (comp (ref "D122")
      (value "BAT42")
      (footprint "eagle-import:DO34-5")
      (libsource (lib "eagle-import") (part "BAT42"))
    )
    (comp (ref "D123")
      (value "BAT42")
      (footprint "eagle-import:DO34-5")
      (libsource (lib "eagle-import") (part "BAT42"))
    )
    (comp (ref "D125")
      (value "BAT42")
      (footprint "eagle-import:DO34-5")
      (libsource (lib "eagle-import") (part "BAT42"))
    )
    (comp (ref "D126")
      (value "BAT42")
      (footprint "eagle-import:DO34-5")
      (libsource (lib "eagle-import") (part "BAT42"))
    )
    (comp (ref "D128")
      (value "BAT42")
      (footprint "eagle-import:DO34-5")
      (libsource (lib "eagle-import") (part "BAT42"))
    )
    (comp (ref "D129")
      (value "BAT42")
      (footprint "eagle-import:DO34-5")
      (libsource (lib "eagle-import") (part "BAT42"))
    )
    (comp (ref "D131")
      (value "BAT42")
      (footprint "eagle-import:DO34-5")
      (libsource (lib "eagle-import") (part "BAT42"))
    )
    (comp (ref "D132")
      (value "BAT42")
      (footprint "eagle-import:DO34-5")
      (libsource (lib "eagle-import") (part "BAT42"))
    )
    (comp (ref "D134")
      (value "BAT42")
      (footprint "eagle-import:DO34-5")
      (libsource (lib "eagle-import") (part "BAT42"))
    )
    (comp (ref "D135")
      (value "BAT42")
      (footprint "eagle-import:DO34-5")
      (libsource (lib "eagle-import") (part "BAT42"))
    )
    (comp (ref "D137")
      (value "BAT42")
      (footprint "eagle-import:DO34-5")
      (libsource (lib "eagle-import") (part "BAT42"))
    )
    (comp (ref "D138")
      (value "BAT42")
      (footprint "eagle-import:DO34-5")
      (libsource (lib "eagle-import") (part "BAT42"))
    )
    (comp (ref "D140")
      (value "BAT42")
      (footprint "eagle-import:DO34-5")
      (libsource (lib "eagle-import") (part "BAT42"))
    )
    (comp (ref "D141")
      (value "BAT42")
      (footprint "eagle-import:DO34-5")
      (libsource (lib "eagle-import") (part "BAT42"))
    )
    (comp (ref "D143")
      (value "BAT42")
      (footprint "eagle-import:DO34-5")
      (libsource (lib "eagle-import") (part "BAT42"))
    )
    (comp (ref "D144")
      (value "BAT42")
      (footprint "eagle-import:DO34-5")
      (libsource (lib "eagle-import") (part "BAT42"))
    )
    (comp (ref "R41")
      (value "1k")
      (footprint "eagle-import:R_P2INCH")
      (libsource (lib "eagle-import") (part "R_P2INCH"))
    )
    (comp (ref "R42")
      (value "1k")
      (footprint "eagle-import:R_P2INCH")
      (libsource (lib "eagle-import") (part "R_P2INCH"))
    )
    (comp (ref "R43")
      (value "1k")
      (footprint "eagle-import:R_P2INCH")
      (libsource (lib "eagle-import") (part "R_P2INCH"))
    )
    (comp (ref "R44")
      (value "1k")
      (footprint "eagle-import:R_P2INCH")
      (libsource (lib "eagle-import") (part "R_P2INCH"))
    )
    (comp (ref "R45")
      (value "1k")
      (footprint "eagle-import:R_P2INCH")
      (libsource (lib "eagle-import") (part "R_P2INCH"))
    )
    (comp (ref "R46")
      (value "1k")
      (footprint "eagle-import:R_P2INCH")
      (libsource (lib "eagle-import") (part "R_P2INCH"))
    )
    (comp (ref "R47")
      (value "1k")
      (footprint "eagle-import:R_P2INCH")
      (libsource (lib "eagle-import") (part "R_P2INCH"))
    )
    (comp (ref "R48")
      (value "1k")
      (footprint "eagle-import:R_P2INCH")
      (libsource (lib "eagle-import") (part "R_P2INCH"))
    )
    (comp (ref "D98")
      (value "BAT42")
      (footprint "eagle-import:DO34-5")
      (libsource (lib "eagle-import") (part "BAT42"))
    )
    (comp (ref "D99")
      (value "BAT42")
      (footprint "eagle-import:DO34-5")
      (libsource (lib "eagle-import") (part "BAT42"))
    )
    (comp (ref "D101")
      (value "BAT42")
      (footprint "eagle-import:DO34-5")
      (libsource (lib "eagle-import") (part "BAT42"))
    )
    (comp (ref "D102")
      (value "BAT42")
      (footprint "eagle-import:DO34-5")
      (libsource (lib "eagle-import") (part "BAT42"))
    )
    (comp (ref "D104")
      (value "BAT42")
      (footprint "eagle-import:DO34-5")
      (libsource (lib "eagle-import") (part "BAT42"))
    )
    (comp (ref "D105")
      (value "BAT42")
      (footprint "eagle-import:DO34-5")
      (libsource (lib "eagle-import") (part "BAT42"))
    )
    (comp (ref "D107")
      (value "BAT42")
      (footprint "eagle-import:DO34-5")
      (libsource (lib "eagle-import") (part "BAT42"))
    )
    (comp (ref "D108")
      (value "BAT42")
      (footprint "eagle-import:DO34-5")
      (libsource (lib "eagle-import") (part "BAT42"))
    )
    (comp (ref "D110")
      (value "BAT42")
      (footprint "eagle-import:DO34-5")
      (libsource (lib "eagle-import") (part "BAT42"))
    )
    (comp (ref "D111")
      (value "BAT42")
      (footprint "eagle-import:DO34-5")
      (libsource (lib "eagle-import") (part "BAT42"))
    )
    (comp (ref "D113")
      (value "BAT42")
      (footprint "eagle-import:DO34-5")
      (libsource (lib "eagle-import") (part "BAT42"))
    )
    (comp (ref "D114")
      (value "BAT42")
      (footprint "eagle-import:DO34-5")
      (libsource (lib "eagle-import") (part "BAT42"))
    )
    (comp (ref "D116")
      (value "BAT42")
      (footprint "eagle-import:DO34-5")
      (libsource (lib "eagle-import") (part "BAT42"))
    )
    (comp (ref "D117")
      (value "BAT42")
      (footprint "eagle-import:DO34-5")
      (libsource (lib "eagle-import") (part "BAT42"))
    )
    (comp (ref "D119")
      (value "BAT42")
      (footprint "eagle-import:DO34-5")
      (libsource (lib "eagle-import") (part "BAT42"))
    )
    (comp (ref "D120")
      (value "BAT42")
      (footprint "eagle-import:DO34-5")
      (libsource (lib "eagle-import") (part "BAT42"))
    )
    (comp (ref "R33")
      (value "1k")
      (footprint "eagle-import:R_P2INCH")
      (libsource (lib "eagle-import") (part "R_P2INCH"))
    )
    (comp (ref "R34")
      (value "1k")
      (footprint "eagle-import:R_P2INCH")
      (libsource (lib "eagle-import") (part "R_P2INCH"))
    )
    (comp (ref "R35")
      (value "1k")
      (footprint "eagle-import:R_P2INCH")
      (libsource (lib "eagle-import") (part "R_P2INCH"))
    )
    (comp (ref "R36")
      (value "1k")
      (footprint "eagle-import:R_P2INCH")
      (libsource (lib "eagle-import") (part "R_P2INCH"))
    )
    (comp (ref "R37")
      (value "1k")
      (footprint "eagle-import:R_P2INCH")
      (libsource (lib "eagle-import") (part "R_P2INCH"))
    )
    (comp (ref "R38")
      (value "1k")
      (footprint "eagle-import:R_P2INCH")
      (libsource (lib "eagle-import") (part "R_P2INCH"))
    )
    (comp (ref "R39")
      (value "1k")
      (footprint "eagle-import:R_P2INCH")
      (libsource (lib "eagle-import") (part "R_P2INCH"))
    )
    (comp (ref "R40")
      (value "1k")
      (footprint "eagle-import:R_P2INCH")
      (libsource (lib "eagle-import") (part "R_P2INCH"))
    )
    (comp (ref "D50")
      (value "BAT42")
      (footprint "eagle-import:DO34-5")
      (libsource (lib "eagle-import") (part "BAT42"))
    )
    (comp (ref "D51")
      (value "BAT42")
      (footprint "eagle-import:DO34-5")
      (libsource (lib "eagle-import") (part "BAT42"))
    )
    (comp (ref "D53")
      (value "BAT42")
      (footprint "eagle-import:DO34-5")
      (libsource (lib "eagle-import") (part "BAT42"))
    )
    (comp (ref "D54")
      (value "BAT42")
      (footprint "eagle-import:DO34-5")
      (libsource (lib "eagle-import") (part "BAT42"))
    )
    (comp (ref "D56")
      (value "BAT42")
      (footprint "eagle-import:DO34-5")
      (libsource (lib "eagle-import") (part "BAT42"))
    )
    (comp (ref "D57")
      (value "BAT42")
      (footprint "eagle-import:DO34-5")
      (libsource (lib "eagle-import") (part "BAT42"))
    )
    (comp (ref "D59")
      (value "BAT42")
      (footprint "eagle-import:DO34-5")
      (libsource (lib "eagle-import") (part "BAT42"))
    )
    (comp (ref "D60")
      (value "BAT42")
      (footprint "eagle-import:DO34-5")
      (libsource (lib "eagle-import") (part "BAT42"))
    )
    (comp (ref "D62")
      (value "BAT42")
      (footprint "eagle-import:DO34-5")
      (libsource (lib "eagle-import") (part "BAT42"))
    )
    (comp (ref "D63")
      (value "BAT42")
      (footprint "eagle-import:DO34-5")
      (libsource (lib "eagle-import") (part "BAT42"))
    )
    (comp (ref "D65")
      (value "BAT42")
      (footprint "eagle-import:DO34-5")
      (libsource (lib "eagle-import") (part "BAT42"))
    )
    (comp (ref "D66")
      (value "BAT42")
      (footprint "eagle-import:DO34-5")
      (libsource (lib "eagle-import") (part "BAT42"))
    )
    (comp (ref "D68")
      (value "BAT42")
      (footprint "eagle-import:DO34-5")
      (libsource (lib "eagle-import") (part "BAT42"))
    )
    (comp (ref "D69")
      (value "BAT42")
      (footprint "eagle-import:DO34-5")
      (libsource (lib "eagle-import") (part "BAT42"))
    )
    (comp (ref "D71")
      (value "BAT42")
      (footprint "eagle-import:DO34-5")
      (libsource (lib "eagle-import") (part "BAT42"))
    )
    (comp (ref "D72")
      (value "BAT42")
      (footprint "eagle-import:DO34-5")
      (libsource (lib "eagle-import") (part "BAT42"))
    )
    (comp (ref "R17")
      (value "1k")
      (footprint "eagle-import:R_P2INCH")
      (libsource (lib "eagle-import") (part "R_P2INCH"))
    )
    (comp (ref "R18")
      (value "1k")
      (footprint "eagle-import:R_P2INCH")
      (libsource (lib "eagle-import") (part "R_P2INCH"))
    )
    (comp (ref "R19")
      (value "1k")
      (footprint "eagle-import:R_P2INCH")
      (libsource (lib "eagle-import") (part "R_P2INCH"))
    )
    (comp (ref "R20")
      (value "1k")
      (footprint "eagle-import:R_P2INCH")
      (libsource (lib "eagle-import") (part "R_P2INCH"))
    )
    (comp (ref "R21")
      (value "1k")
      (footprint "eagle-import:R_P2INCH")
      (libsource (lib "eagle-import") (part "R_P2INCH"))
    )
    (comp (ref "R22")
      (value "1k")
      (footprint "eagle-import:R_P2INCH")
      (libsource (lib "eagle-import") (part "R_P2INCH"))
    )
    (comp (ref "R23")
      (value "1k")
      (footprint "eagle-import:R_P2INCH")
      (libsource (lib "eagle-import") (part "R_P2INCH"))
    )
    (comp (ref "R24")
      (value "1k")
      (footprint "eagle-import:R_P2INCH")
      (libsource (lib "eagle-import") (part "R_P2INCH"))
    )
    (comp (ref "D146")
      (value "BAT42")
      (footprint "eagle-import:DO34-5")
      (libsource (lib "eagle-import") (part "BAT42"))
    )
    (comp (ref "D147")
      (value "BAT42")
      (footprint "eagle-import:DO34-5")
      (libsource (lib "eagle-import") (part "BAT42"))
    )
    (comp (ref "D149")
      (value "BAT42")
      (footprint "eagle-import:DO34-5")
      (libsource (lib "eagle-import") (part "BAT42"))
    )
    (comp (ref "D150")
      (value "BAT42")
      (footprint "eagle-import:DO34-5")
      (libsource (lib "eagle-import") (part "BAT42"))
    )
    (comp (ref "D152")
      (value "BAT42")
      (footprint "eagle-import:DO34-5")
      (libsource (lib "eagle-import") (part "BAT42"))
    )
    (comp (ref "D153")
      (value "BAT42")
      (footprint "eagle-import:DO34-5")
      (libsource (lib "eagle-import") (part "BAT42"))
    )
    (comp (ref "D155")
      (value "BAT42")
      (footprint "eagle-import:DO34-5")
      (libsource (lib "eagle-import") (part "BAT42"))
    )
    (comp (ref "D156")
      (value "BAT42")
      (footprint "eagle-import:DO34-5")
      (libsource (lib "eagle-import") (part "BAT42"))
    )
    (comp (ref "D158")
      (value "BAT42")
      (footprint "eagle-import:DO34-5")
      (libsource (lib "eagle-import") (part "BAT42"))
    )
    (comp (ref "D159")
      (value "BAT42")
      (footprint "eagle-import:DO34-5")
      (libsource (lib "eagle-import") (part "BAT42"))
    )
    (comp (ref "D161")
      (value "BAT42")
      (footprint "eagle-import:DO34-5")
      (libsource (lib "eagle-import") (part "BAT42"))
    )
    (comp (ref "D162")
      (value "BAT42")
      (footprint "eagle-import:DO34-5")
      (libsource (lib "eagle-import") (part "BAT42"))
    )
    (comp (ref "D164")
      (value "BAT42")
      (footprint "eagle-import:DO34-5")
      (libsource (lib "eagle-import") (part "BAT42"))
    )
    (comp (ref "D165")
      (value "BAT42")
      (footprint "eagle-import:DO34-5")
      (libsource (lib "eagle-import") (part "BAT42"))
    )
    (comp (ref "D167")
      (value "BAT42")
      (footprint "eagle-import:DO34-5")
      (libsource (lib "eagle-import") (part "BAT42"))
    )
    (comp (ref "D168")
      (value "BAT42")
      (footprint "eagle-import:DO34-5")
      (libsource (lib "eagle-import") (part "BAT42"))
    )
    (comp (ref "R49")
      (value "1k")
      (footprint "eagle-import:R_P2INCH")
      (libsource (lib "eagle-import") (part "R_P2INCH"))
    )
    (comp (ref "R50")
      (value "1k")
      (footprint "eagle-import:R_P2INCH")
      (libsource (lib "eagle-import") (part "R_P2INCH"))
    )
    (comp (ref "R51")
      (value "1k")
      (footprint "eagle-import:R_P2INCH")
      (libsource (lib "eagle-import") (part "R_P2INCH"))
    )
    (comp (ref "R52")
      (value "1k")
      (footprint "eagle-import:R_P2INCH")
      (libsource (lib "eagle-import") (part "R_P2INCH"))
    )
    (comp (ref "R53")
      (value "1k")
      (footprint "eagle-import:R_P2INCH")
      (libsource (lib "eagle-import") (part "R_P2INCH"))
    )
    (comp (ref "R54")
      (value "1k")
      (footprint "eagle-import:R_P2INCH")
      (libsource (lib "eagle-import") (part "R_P2INCH"))
    )
    (comp (ref "R55")
      (value "1k")
      (footprint "eagle-import:R_P2INCH")
      (libsource (lib "eagle-import") (part "R_P2INCH"))
    )
    (comp (ref "R56")
      (value "1k")
      (footprint "eagle-import:R_P2INCH")
      (libsource (lib "eagle-import") (part "R_P2INCH"))
    )
    (comp (ref "D2")
      (value "BAT42")
      (footprint "eagle-import:DO34-5")
      (libsource (lib "eagle-import") (part "BAT42"))
    )
    (comp (ref "D3")
      (value "BAT42")
      (footprint "eagle-import:DO34-5")
      (libsource (lib "eagle-import") (part "BAT42"))
    )
    (comp (ref "D5")
      (value "BAT42")
      (footprint "eagle-import:DO34-5")
      (libsource (lib "eagle-import") (part "BAT42"))
    )
    (comp (ref "D6")
      (value "BAT42")
      (footprint "eagle-import:DO34-5")
      (libsource (lib "eagle-import") (part "BAT42"))
    )
    (comp (ref "D8")
      (value "BAT42")
      (footprint "eagle-import:DO34-5")
      (libsource (lib "eagle-import") (part "BAT42"))
    )
    (comp (ref "D9")
      (value "BAT42")
      (footprint "eagle-import:DO34-5")
      (libsource (lib "eagle-import") (part "BAT42"))
    )
    (comp (ref "D11")
      (value "BAT42")
      (footprint "eagle-import:DO34-5")
      (libsource (lib "eagle-import") (part "BAT42"))
    )
    (comp (ref "D12")
      (value "BAT42")
      (footprint "eagle-import:DO34-5")
      (libsource (lib "eagle-import") (part "BAT42"))
    )
    (comp (ref "D14")
      (value "BAT42")
      (footprint "eagle-import:DO34-5")
      (libsource (lib "eagle-import") (part "BAT42"))
    )
    (comp (ref "D15")
      (value "BAT42")
      (footprint "eagle-import:DO34-5")
      (libsource (lib "eagle-import") (part "BAT42"))
    )
    (comp (ref "D17")
      (value "BAT42")
      (footprint "eagle-import:DO34-5")
      (libsource (lib "eagle-import") (part "BAT42"))
    )
    (comp (ref "D18")
      (value "BAT42")
      (footprint "eagle-import:DO34-5")
      (libsource (lib "eagle-import") (part "BAT42"))
    )
    (comp (ref "D20")
      (value "BAT42")
      (footprint "eagle-import:DO34-5")
      (libsource (lib "eagle-import") (part "BAT42"))
    )
    (comp (ref "D21")
      (value "BAT42")
      (footprint "eagle-import:DO34-5")
      (libsource (lib "eagle-import") (part "BAT42"))
    )
    (comp (ref "D23")
      (value "BAT42")
      (footprint "eagle-import:DO34-5")
      (libsource (lib "eagle-import") (part "BAT42"))
    )
    (comp (ref "D24")
      (value "BAT42")
      (footprint "eagle-import:DO34-5")
      (libsource (lib "eagle-import") (part "BAT42"))
    )
    (comp (ref "R1")
      (value "1k")
      (footprint "eagle-import:R_P2INCH")
      (libsource (lib "eagle-import") (part "R_P2INCH"))
    )
    (comp (ref "R2")
      (value "1k")
      (footprint "eagle-import:R_P2INCH")
      (libsource (lib "eagle-import") (part "R_P2INCH"))
    )
    (comp (ref "R3")
      (value "1k")
      (footprint "eagle-import:R_P2INCH")
      (libsource (lib "eagle-import") (part "R_P2INCH"))
    )
    (comp (ref "R4")
      (value "1k")
      (footprint "eagle-import:R_P2INCH")
      (libsource (lib "eagle-import") (part "R_P2INCH"))
    )
    (comp (ref "R5")
      (value "1k")
      (footprint "eagle-import:R_P2INCH")
      (libsource (lib "eagle-import") (part "R_P2INCH"))
    )
    (comp (ref "R6")
      (value "1k")
      (footprint "eagle-import:R_P2INCH")
      (libsource (lib "eagle-import") (part "R_P2INCH"))
    )
    (comp (ref "R7")
      (value "1k")
      (footprint "eagle-import:R_P2INCH")
      (libsource (lib "eagle-import") (part "R_P2INCH"))
    )
    (comp (ref "R8")
      (value "1k")
      (footprint "eagle-import:R_P2INCH")
      (libsource (lib "eagle-import") (part "R_P2INCH"))
    )
  )
  (nets
    (net (code "1") (name "+5V") (class "Default")
      (node (ref "C1") (pin "1") (pinfunction "1_1") (pintype "passive"))
      (node (ref "C2") (pin "2") (pinfunction "2_2") (pintype "passive"))
      (node (ref "C3") (pin "2") (pinfunction "2_2") (pintype "passive"))
      (node (ref "C4") (pin "2") (pinfunction "2_2") (pintype "passive"))
      (node (ref "D101") (pin "C") (pinfunction "C_C") (pintype "passive"))
      (node (ref "D104") (pin "C") (pinfunction "C_C") (pintype "passive"))
      (node (ref "D107") (pin "C") (pinfunction "C_C") (pintype "passive"))
      (node (ref "D11") (pin "C") (pinfunction "C_C") (pintype "passive"))
      (node (ref "D110") (pin "C") (pinfunction "C_C") (pintype "passive"))
      (node (ref "D113") (pin "C") (pinfunction "C_C") (pintype "passive"))
      (node (ref "D116") (pin "C") (pinfunction "C_C") (pintype "passive"))
      (node (ref "D119") (pin "C") (pinfunction "C_C") (pintype "passive"))
      (node (ref "D122") (pin "C") (pinfunction "C_C") (pintype "passive"))
      (node (ref "D125") (pin "C") (pinfunction "C_C") (pintype "passive"))
      (node (ref "D128") (pin "C") (pinfunction "C_C") (pintype "passive"))
      (node (ref "D131") (pin "C") (pinfunction "C_C") (pintype "passive"))
      (node (ref "D134") (pin "C") (pinfunction "C_C") (pintype "passive"))
      (node (ref "D137") (pin "C") (pinfunction "C_C") (pintype "passive"))
      (node (ref "D14") (pin "C") (pinfunction "C_C") (pintype "passive"))
      (node (ref "D140") (pin "C") (pinfunction "C_C") (pintype "passive"))
      (node (ref "D143") (pin "C") (pinfunction "C_C") (pintype "passive"))
      (node (ref "D146") (pin "C") (pinfunction "C_C") (pintype "passive"))
      (node (ref "D149") (pin "C") (pinfunction "C_C") (pintype "passive"))
      (node (ref "D152") (pin "C") (pinfunction "C_C") (pintype "passive"))
      (node (ref "D155") (pin "C") (pinfunction "C_C") (pintype "passive"))
      (node (ref "D158") (pin "C") (pinfunction "C_C") (pintype "passive"))
      (node (ref "D161") (pin "C") (pinfunction "C_C") (pintype "passive"))
      (node (ref "D164") (pin "C") (pinfunction "C_C") (pintype "passive"))
      (node (ref "D167") (pin "C") (pinfunction "C_C") (pintype "passive"))
      (node (ref "D17") (pin "C") (pinfunction "C_C") (pintype "passive"))
      (node (ref "D170") (pin "C") (pinfunction "C_C") (pintype "passive"))
      (node (ref "D173") (pin "C") (pinfunction "C_C") (pintype "passive"))
      (node (ref "D176") (pin "C") (pinfunction "C_C") (pintype "passive"))
      (node (ref "D179") (pin "C") (pinfunction "C_C") (pintype "passive"))
      (node (ref "D182") (pin "C") (pinfunction "C_C") (pintype "passive"))
      (node (ref "D185") (pin "C") (pinfunction "C_C") (pintype "passive"))
      (node (ref "D188") (pin "C") (pinfunction "C_C") (pintype "passive"))
      (node (ref "D191") (pin "C") (pinfunction "C_C") (pintype "passive"))
      (node (ref "D2") (pin "C") (pinfunction "C_C") (pintype "passive"))
      (node (ref "D20") (pin "C") (pinfunction "C_C") (pintype "passive"))
      (node (ref "D23") (pin "C") (pinfunction "C_C") (pintype "passive"))
      (node (ref "D26") (pin "C") (pinfunction "C_C") (pintype "passive"))
      (node (ref "D29") (pin "C") (pinfunction "C_C") (pintype "passive"))
      (node (ref "D32") (pin "C") (pinfunction "C_C") (pintype "passive"))
      (node (ref "D35") (pin "C") (pinfunction "C_C") (pintype "passive"))
      (node (ref "D38") (pin "C") (pinfunction "C_C") (pintype "passive"))
      (node (ref "D41") (pin "C") (pinfunction "C_C") (pintype "passive"))
      (node (ref "D44") (pin "C") (pinfunction "C_C") (pintype "passive"))
      (node (ref "D47") (pin "C") (pinfunction "C_C") (pintype "passive"))
      (node (ref "D5") (pin "C") (pinfunction "C_C") (pintype "passive"))
      (node (ref "D50") (pin "C") (pinfunction "C_C") (pintype "passive"))
      (node (ref "D53") (pin "C") (pinfunction "C_C") (pintype "passive"))
      (node (ref "D56") (pin "C") (pinfunction "C_C") (pintype "passive"))
      (node (ref "D59") (pin "C") (pinfunction "C_C") (pintype "passive"))
      (node (ref "D62") (pin "C") (pinfunction "C_C") (pintype "passive"))
      (node (ref "D65") (pin "C") (pinfunction "C_C") (pintype "passive"))
      (node (ref "D68") (pin "C") (pinfunction "C_C") (pintype "passive"))
      (node (ref "D71") (pin "C") (pinfunction "C_C") (pintype "passive"))
      (node (ref "D74") (pin "C") (pinfunction "C_C") (pintype "passive"))
      (node (ref "D77") (pin "C") (pinfunction "C_C") (pintype "passive"))
      (node (ref "D8") (pin "C") (pinfunction "C_C") (pintype "passive"))
      (node (ref "D80") (pin "C") (pinfunction "C_C") (pintype "passive"))
      (node (ref "D83") (pin "C") (pinfunction "C_C") (pintype "passive"))
      (node (ref "D86") (pin "C") (pinfunction "C_C") (pintype "passive"))
      (node (ref "D89") (pin "C") (pinfunction "C_C") (pintype "passive"))
      (node (ref "D92") (pin "C") (pinfunction "C_C") (pintype "passive"))
      (node (ref "D95") (pin "C") (pinfunction "C_C") (pintype "passive"))
      (node (ref "D98") (pin "C") (pinfunction "C_C") (pintype "passive"))
      (node (ref "PP1") (pin "1") (pinfunction "P$1_1") (pintype "bidirectional"))
      (node (ref "PP2") (pin "1") (pinfunction "P$1_1") (pintype "bidirectional"))
      (node (ref "PP3") (pin "1") (pinfunction "P$1_1") (pintype "bidirectional"))
      (node (ref "R65") (pin "2") (pinfunction "2_2") (pintype "passive"))
    )
    (net (code "2") (name "D0") (class "Default")
      (node (ref "D2") (pin "A") (pinfunction "A_A") (pintype "passive"))
      (node (ref "D3") (pin "C") (pinfunction "C_C") (pintype "passive"))
      (node (ref "J5") (pin "1") (pinfunction "1_1") (pintype "bidirectional"))
      (node (ref "R1") (pin "2") (pinfunction "2_2") (pintype "passive"))
    )
    (net (code "3") (name "D1") (class "Default")
      (node (ref "D5") (pin "A") (pinfunction "A_A") (pintype "passive"))
      (node (ref "D6") (pin "C") (pinfunction "C_C") (pintype "passive"))
      (node (ref "J5") (pin "2") (pinfunction "2_2") (pintype "bidirectional"))
      (node (ref "R2") (pin "2") (pinfunction "2_2") (pintype "passive"))
    )
    (net (code "4") (name "D2") (class "Default")
      (node (ref "D8") (pin "A") (pinfunction "A_A") (pintype "passive"))
      (node (ref "D9") (pin "C") (pinfunction "C_C") (pintype "passive"))
      (node (ref "J5") (pin "3") (pinfunction "3_3") (pintype "bidirectional"))
      (node (ref "R3") (pin "2") (pinfunction "2_2") (pintype "passive"))
    )
    (net (code "5") (name "D3") (class "Default")
      (node (ref "D11") (pin "A") (pinfunction "A_A") (pintype "passive"))
      (node (ref "D12") (pin "C") (pinfunction "C_C") (pintype "passive"))
      (node (ref "J5") (pin "4") (pinfunction "4_4") (pintype "bidirectional"))
      (node (ref "R4") (pin "2") (pinfunction "2_2") (pintype "passive"))
    )
    (net (code "6") (name "D4") (class "Default")
      (node (ref "D14") (pin "A") (pinfunction "A_A") (pintype "passive"))
      (node (ref "D15") (pin "C") (pinfunction "C_C") (pintype "passive"))
      (node (ref "J5") (pin "5") (pinfunction "5_5") (pintype "bidirectional"))
      (node (ref "R5") (pin "2") (pinfunction "2_2") (pintype "passive"))
    )
    (net (code "7") (name "D5") (class "Default")
      (node (ref "D17") (pin "A") (pinfunction "A_A") (pintype "passive"))
      (node (ref "D18") (pin "C") (pinfunction "C_C") (pintype "passive"))
      (node (ref "J5") (pin "6") (pinfunction "6_6") (pintype "bidirectional"))
      (node (ref "R6") (pin "2") (pinfunction "2_2") (pintype "passive"))
    )
    (net (code "8") (name "D6") (class "Default")
      (node (ref "D20") (pin "A") (pinfunction "A_A") (pintype "passive"))
      (node (ref "D21") (pin "C") (pinfunction "C_C") (pintype "passive"))
      (node (ref "J5") (pin "7") (pinfunction "7_7") (pintype "bidirectional"))
      (node (ref "R7") (pin "2") (pinfunction "2_2") (pintype "passive"))
    )
    (net (code "9") (name "D7") (class "Default")
      (node (ref "D23") (pin "A") (pinfunction "A_A") (pintype "passive"))
      (node (ref "D24") (pin "C") (pinfunction "C_C") (pintype "passive"))
      (node (ref "J5") (pin "8") (pinfunction "8_8") (pintype "bidirectional"))
      (node (ref "R8") (pin "2") (pinfunction "2_2") (pintype "passive"))
    )
    (net (code "10") (name "D8") (class "Default")
      (node (ref "D26") (pin "A") (pinfunction "A_A") (pintype "passive"))
      (node (ref "D27") (pin "C") (pinfunction "C_C") (pintype "passive"))
      (node (ref "J5") (pin "9") (pinfunction "9_9") (pintype "bidirectional"))
      (node (ref "R9") (pin "2") (pinfunction "2_2") (pintype "passive"))
    )
    (net (code "11") (name "D9") (class "Default")
      (node (ref "D29") (pin "A") (pinfunction "A_A") (pintype "passive"))
      (node (ref "D30") (pin "C") (pinfunction "C_C") (pintype "passive"))
      (node (ref "J5") (pin "10") (pinfunction "10_10") (pintype "bidirectional"))
      (node (ref "R10") (pin "2") (pinfunction "2_2") (pintype "passive"))
    )
    (net (code "12") (name "D10") (class "Default")
      (node (ref "D32") (pin "A") (pinfunction "A_A") (pintype "passive"))
      (node (ref "D33") (pin "C") (pinfunction "C_C") (pintype "passive"))
      (node (ref "J5") (pin "11") (pinfunction "11_11") (pintype "bidirectional"))
      (node (ref "R11") (pin "2") (pinfunction "2_2") (pintype "passive"))
    )
    (net (code "13") (name "D11") (class "Default")
      (node (ref "D35") (pin "A") (pinfunction "A_A") (pintype "passive"))
      (node (ref "D36") (pin "C") (pinfunction "C_C") (pintype "passive"))
      (node (ref "J5") (pin "12") (pinfunction "12_12") (pintype "bidirectional"))
      (node (ref "R12") (pin "2") (pinfunction "2_2") (pintype "passive"))
    )
    (net (code "14") (name "D12") (class "Default")
      (node (ref "D38") (pin "A") (pinfunction "A_A") (pintype "passive"))
      (node (ref "D39") (pin "C") (pinfunction "C_C") (pintype "passive"))
      (node (ref "J5") (pin "13") (pinfunction "13_13") (pintype "bidirectional"))
      (node (ref "R13") (pin "2") (pinfunction "2_2") (pintype "passive"))
    )
    (net (code "15") (name "D13") (class "Default")
      (node (ref "D41") (pin "A") (pinfunction "A_A") (pintype "passive"))
      (node (ref "D42") (pin "C") (pinfunction "C_C") (pintype "passive"))
      (node (ref "J5") (pin "14") (pinfunction "14_14") (pintype "bidirectional"))
      (node (ref "R14") (pin "2") (pinfunction "2_2") (pintype "passive"))
    )
    (net (code "16") (name "D14") (class "Default")
      (node (ref "D44") (pin "A") (pinfunction "A_A") (pintype "passive"))
      (node (ref "D45") (pin "C") (pinfunction "C_C") (pintype "passive"))
      (node (ref "J5") (pin "15") (pinfunction "15_15") (pintype "bidirectional"))
      (node (ref "R15") (pin "2") (pinfunction "2_2") (pintype "passive"))
    )
    (net (code "17") (name "D15") (class "Default")
      (node (ref "D47") (pin "A") (pinfunction "A_A") (pintype "passive"))
      (node (ref "D48") (pin "C") (pinfunction "C_C") (pintype "passive"))
      (node (ref "J5") (pin "16") (pinfunction "16_16") (pintype "bidirectional"))
      (node (ref "R16") (pin "2") (pinfunction "2_2") (pintype "passive"))
    )
    (net (code "18") (name "D16") (class "Default")
      (node (ref "D50") (pin "A") (pinfunction "A_A") (pintype "passive"))
      (node (ref "D51") (pin "C") (pinfunction "C_C") (pintype "passive"))
      (node (ref "J5") (pin "17") (pinfunction "17_17") (pintype "bidirectional"))
      (node (ref "R17") (pin "2") (pinfunction "2_2") (pintype "passive"))
    )
    (net (code "19") (name "D17") (class "Default")
      (node (ref "D53") (pin "A") (pinfunction "A_A") (pintype "passive"))
      (node (ref "D54") (pin "C") (pinfunction "C_C") (pintype "passive"))
      (node (ref "J5") (pin "18") (pinfunction "18_18") (pintype "bidirectional"))
      (node (ref "R18") (pin "2") (pinfunction "2_2") (pintype "passive"))
    )
    (net (code "20") (name "D18") (class "Default")
      (node (ref "D56") (pin "A") (pinfunction "A_A") (pintype "passive"))
      (node (ref "D57") (pin "C") (pinfunction "C_C") (pintype "passive"))
      (node (ref "J5") (pin "19") (pinfunction "19_19") (pintype "bidirectional"))
      (node (ref "R19") (pin "2") (pinfunction "2_2") (pintype "passive"))
    )
    (net (code "21") (name "D19") (class "Default")
      (node (ref "D59") (pin "A") (pinfunction "A_A") (pintype "passive"))
      (node (ref "D60") (pin "C") (pinfunction "C_C") (pintype "passive"))
      (node (ref "J5") (pin "20") (pinfunction "20_20") (pintype "bidirectional"))
      (node (ref "R20") (pin "2") (pinfunction "2_2") (pintype "passive"))
    )
    (net (code "22") (name "D20") (class "Default")
      (node (ref "D62") (pin "A") (pinfunction "A_A") (pintype "passive"))
      (node (ref "D63") (pin "C") (pinfunction "C_C") (pintype "passive"))
      (node (ref "J5") (pin "21") (pinfunction "21_21") (pintype "bidirectional"))
      (node (ref "R21") (pin "2") (pinfunction "2_2") (pintype "passive"))
    )
    (net (code "23") (name "D21") (class "Default")
      (node (ref "D65") (pin "A") (pinfunction "A_A") (pintype "passive"))
      (node (ref "D66") (pin "C") (pinfunction "C_C") (pintype "passive"))
      (node (ref "J5") (pin "22") (pinfunction "22_22") (pintype "bidirectional"))
      (node (ref "R22") (pin "2") (pinfunction "2_2") (pintype "passive"))
    )
    (net (code "24") (name "D22") (class "Default")
      (node (ref "D68") (pin "A") (pinfunction "A_A") (pintype "passive"))
      (node (ref "D69") (pin "C") (pinfunction "C_C") (pintype "passive"))
      (node (ref "J5") (pin "23") (pinfunction "23_23") (pintype "bidirectional"))
      (node (ref "R23") (pin "2") (pinfunction "2_2") (pintype "passive"))
    )
    (net (code "25") (name "D23") (class "Default")
      (node (ref "D71") (pin "A") (pinfunction "A_A") (pintype "passive"))
      (node (ref "D72") (pin "C") (pinfunction "C_C") (pintype "passive"))
      (node (ref "J5") (pin "24") (pinfunction "24_24") (pintype "bidirectional"))
      (node (ref "R24") (pin "2") (pinfunction "2_2") (pintype "passive"))
    )
    (net (code "26") (name "D24") (class "Default")
      (node (ref "D74") (pin "A") (pinfunction "A_A") (pintype "passive"))
      (node (ref "D75") (pin "C") (pinfunction "C_C") (pintype "passive"))
      (node (ref "J5") (pin "25") (pinfunction "25_25") (pintype "bidirectional"))
      (node (ref "R25") (pin "2") (pinfunction "2_2") (pintype "passive"))
    )
    (net (code "27") (name "D25") (class "Default")
      (node (ref "D77") (pin "A") (pinfunction "A_A") (pintype "passive"))
      (node (ref "D78") (pin "C") (pinfunction "C_C") (pintype "passive"))
      (node (ref "J5") (pin "26") (pinfunction "26_26") (pintype "bidirectional"))
      (node (ref "R26") (pin "2") (pinfunction "2_2") (pintype "passive"))
    )
    (net (code "28") (name "D26") (class "Default")
      (node (ref "D80") (pin "A") (pinfunction "A_A") (pintype "passive"))
      (node (ref "D81") (pin "C") (pinfunction "C_C") (pintype "passive"))
      (node (ref "J5") (pin "27") (pinfunction "27_27") (pintype "bidirectional"))
      (node (ref "R27") (pin "2") (pinfunction "2_2") (pintype "passive"))
    )
    (net (code "29") (name "D27") (class "Default")
      (node (ref "D83") (pin "A") (pinfunction "A_A") (pintype "passive"))
      (node (ref "D84") (pin "C") (pinfunction "C_C") (pintype "passive"))
      (node (ref "J5") (pin "28") (pinfunction "28_28") (pintype "bidirectional"))
      (node (ref "R28") (pin "2") (pinfunction "2_2") (pintype "passive"))
    )
    (net (code "30") (name "D28") (class "Default")
      (node (ref "D86") (pin "A") (pinfunction "A_A") (pintype "passive"))
      (node (ref "D87") (pin "C") (pinfunction "C_C") (pintype "passive"))
      (node (ref "J5") (pin "29") (pinfunction "29_29") (pintype "bidirectional"))
      (node (ref "R29") (pin "2") (pinfunction "2_2") (pintype "passive"))
    )
    (net (code "31") (name "D29") (class "Default")
      (node (ref "D89") (pin "A") (pinfunction "A_A") (pintype "passive"))
      (node (ref "D90") (pin "C") (pinfunction "C_C") (pintype "passive"))
      (node (ref "J5") (pin "30") (pinfunction "30_30") (pintype "bidirectional"))
      (node (ref "R30") (pin "2") (pinfunction "2_2") (pintype "passive"))
    )
    (net (code "32") (name "D30") (class "Default")
      (node (ref "D92") (pin "A") (pinfunction "A_A") (pintype "passive"))
      (node (ref "D93") (pin "C") (pinfunction "C_C") (pintype "passive"))
      (node (ref "J5") (pin "31") (pinfunction "31_31") (pintype "bidirectional"))
      (node (ref "R31") (pin "2") (pinfunction "2_2") (pintype "passive"))
    )
    (net (code "33") (name "D31") (class "Default")
      (node (ref "D95") (pin "A") (pinfunction "A_A") (pintype "passive"))
      (node (ref "D96") (pin "C") (pinfunction "C_C") (pintype "passive"))
      (node (ref "J5") (pin "32") (pinfunction "32_32") (pintype "bidirectional"))
      (node (ref "R32") (pin "2") (pinfunction "2_2") (pintype "passive"))
    )
    (net (code "34") (name "D32") (class "Default")
      (node (ref "D98") (pin "A") (pinfunction "A_A") (pintype "passive"))
      (node (ref "D99") (pin "C") (pinfunction "C_C") (pintype "passive"))
      (node (ref "J5") (pin "33") (pinfunction "33_33") (pintype "bidirectional"))
      (node (ref "R33") (pin "2") (pinfunction "2_2") (pintype "passive"))
    )
    (net (code "35") (name "D33") (class "Default")
      (node (ref "D101") (pin "A") (pinfunction "A_A") (pintype "passive"))
      (node (ref "D102") (pin "C") (pinfunction "C_C") (pintype "passive"))
      (node (ref "J5") (pin "34") (pinfunction "34_34") (pintype "bidirectional"))
      (node (ref "R34") (pin "2") (pinfunction "2_2") (pintype "passive"))
    )
    (net (code "36") (name "D34") (class "Default")
      (node (ref "D104") (pin "A") (pinfunction "A_A") (pintype "passive"))
      (node (ref "D105") (pin "C") (pinfunction "C_C") (pintype "passive"))
      (node (ref "J5") (pin "35") (pinfunction "35_35") (pintype "bidirectional"))
      (node (ref "R35") (pin "2") (pinfunction "2_2") (pintype "passive"))
    )
    (net (code "37") (name "D35") (class "Default")
      (node (ref "D107") (pin "A") (pinfunction "A_A") (pintype "passive"))
      (node (ref "D108") (pin "C") (pinfunction "C_C") (pintype "passive"))
      (node (ref "J5") (pin "36") (pinfunction "36_36") (pintype "bidirectional"))
      (node (ref "R36") (pin "2") (pinfunction "2_2") (pintype "passive"))
    )
    (net (code "38") (name "D36") (class "Default")
      (node (ref "D110") (pin "A") (pinfunction "A_A") (pintype "passive"))
      (node (ref "D111") (pin "C") (pinfunction "C_C") (pintype "passive"))
      (node (ref "J5") (pin "37") (pinfunction "37_37") (pintype "bidirectional"))
      (node (ref "R37") (pin "2") (pinfunction "2_2") (pintype "passive"))
    )
    (net (code "39") (name "D37") (class "Default")
      (node (ref "D113") (pin "A") (pinfunction "A_A") (pintype "passive"))
      (node (ref "D114") (pin "C") (pinfunction "C_C") (pintype "passive"))
      (node (ref "J5") (pin "38") (pinfunction "38_38") (pintype "bidirectional"))
      (node (ref "R38") (pin "2") (pinfunction "2_2") (pintype "passive"))
    )
    (net (code "40") (name "D38") (class "Default")
      (node (ref "D116") (pin "A") (pinfunction "A_A") (pintype "passive"))
      (node (ref "D117") (pin "C") (pinfunction "C_C") (pintype "passive"))
      (node (ref "J5") (pin "39") (pinfunction "39_39") (pintype "bidirectional"))
      (node (ref "R39") (pin "2") (pinfunction "2_2") (pintype "passive"))
    )
    (net (code "41") (name "D39") (class "Default")
      (node (ref "D119") (pin "A") (pinfunction "A_A") (pintype "passive"))
      (node (ref "D120") (pin "C") (pinfunction "C_C") (pintype "passive"))
      (node (ref "J5") (pin "40") (pinfunction "40_40") (pintype "bidirectional"))
      (node (ref "R40") (pin "2") (pinfunction "2_2") (pintype "passive"))
    )
    (net (code "42") (name "D40") (class "Default")
      (node (ref "D122") (pin "A") (pinfunction "A_A") (pintype "passive"))
      (node (ref "D123") (pin "C") (pinfunction "C_C") (pintype "passive"))
      (node (ref "J5") (pin "41") (pinfunction "41_41") (pintype "bidirectional"))
      (node (ref "R41") (pin "2") (pinfunction "2_2") (pintype "passive"))
    )
    (net (code "43") (name "D41") (class "Default")
      (node (ref "D125") (pin "A") (pinfunction "A_A") (pintype "passive"))
      (node (ref "D126") (pin "C") (pinfunction "C_C") (pintype "passive"))
      (node (ref "J5") (pin "42") (pinfunction "42_42") (pintype "bidirectional"))
      (node (ref "R42") (pin "2") (pinfunction "2_2") (pintype "passive"))
    )
    (net (code "44") (name "D42") (class "Default")
      (node (ref "D128") (pin "A") (pinfunction "A_A") (pintype "passive"))
      (node (ref "D129") (pin "C") (pinfunction "C_C") (pintype "passive"))
      (node (ref "J5") (pin "43") (pinfunction "43_43") (pintype "bidirectional"))
      (node (ref "R43") (pin "2") (pinfunction "2_2") (pintype "passive"))
    )
    (net (code "45") (name "D43") (class "Default")
      (node (ref "D131") (pin "A") (pinfunction "A_A") (pintype "passive"))
      (node (ref "D132") (pin "C") (pinfunction "C_C") (pintype "passive"))
      (node (ref "J5") (pin "44") (pinfunction "44_44") (pintype "bidirectional"))
      (node (ref "R44") (pin "2") (pinfunction "2_2") (pintype "passive"))
    )
    (net (code "46") (name "D44") (class "Default")
      (node (ref "D134") (pin "A") (pinfunction "A_A") (pintype "passive"))
      (node (ref "D135") (pin "C") (pinfunction "C_C") (pintype "passive"))
      (node (ref "J5") (pin "45") (pinfunction "45_45") (pintype "bidirectional"))
      (node (ref "R45") (pin "2") (pinfunction "2_2") (pintype "passive"))
    )
    (net (code "47") (name "D45") (class "Default")
      (node (ref "D137") (pin "A") (pinfunction "A_A") (pintype "passive"))
      (node (ref "D138") (pin "C") (pinfunction "C_C") (pintype "passive"))
      (node (ref "J5") (pin "46") (pinfunction "46_46") (pintype "bidirectional"))
      (node (ref "R46") (pin "2") (pinfunction "2_2") (pintype "passive"))
    )
    (net (code "48") (name "D46") (class "Default")
      (node (ref "D140") (pin "A") (pinfunction "A_A") (pintype "passive"))
      (node (ref "D141") (pin "C") (pinfunction "C_C") (pintype "passive"))
      (node (ref "J5") (pin "47") (pinfunction "47_47") (pintype "bidirectional"))
      (node (ref "R47") (pin "2") (pinfunction "2_2") (pintype "passive"))
    )
    (net (code "49") (name "D47") (class "Default")
      (node (ref "D143") (pin "A") (pinfunction "A_A") (pintype "passive"))
      (node (ref "D144") (pin "C") (pinfunction "C_C") (pintype "passive"))
      (node (ref "J5") (pin "48") (pinfunction "48_48") (pintype "bidirectional"))
      (node (ref "R48") (pin "2") (pinfunction "2_2") (pintype "passive"))
    )
    (net (code "50") (name "D48") (class "Default")
      (node (ref "D146") (pin "A") (pinfunction "A_A") (pintype "passive"))
      (node (ref "D147") (pin "C") (pinfunction "C_C") (pintype "passive"))
      (node (ref "J5") (pin "49") (pinfunction "49_49") (pintype "bidirectional"))
      (node (ref "R49") (pin "2") (pinfunction "2_2") (pintype "passive"))
    )
    (net (code "51") (name "D49") (class "Default")
      (node (ref "D149") (pin "A") (pinfunction "A_A") (pintype "passive"))
      (node (ref "D150") (pin "C") (pinfunction "C_C") (pintype "passive"))
      (node (ref "J5") (pin "50") (pinfunction "50_50") (pintype "bidirectional"))
      (node (ref "R50") (pin "2") (pinfunction "2_2") (pintype "passive"))
    )
    (net (code "52") (name "D50") (class "Default")
      (node (ref "D152") (pin "A") (pinfunction "A_A") (pintype "passive"))
      (node (ref "D153") (pin "C") (pinfunction "C_C") (pintype "passive"))
      (node (ref "J5") (pin "51") (pinfunction "51_51") (pintype "bidirectional"))
      (node (ref "R51") (pin "2") (pinfunction "2_2") (pintype "passive"))
    )
    (net (code "53") (name "D51") (class "Default")
      (node (ref "D155") (pin "A") (pinfunction "A_A") (pintype "passive"))
      (node (ref "D156") (pin "C") (pinfunction "C_C") (pintype "passive"))
      (node (ref "J5") (pin "52") (pinfunction "52_52") (pintype "bidirectional"))
      (node (ref "R52") (pin "2") (pinfunction "2_2") (pintype "passive"))
    )
    (net (code "54") (name "D52") (class "Default")
      (node (ref "D158") (pin "A") (pinfunction "A_A") (pintype "passive"))
      (node (ref "D159") (pin "C") (pinfunction "C_C") (pintype "passive"))
      (node (ref "J5") (pin "53") (pinfunction "53_53") (pintype "bidirectional"))
      (node (ref "R53") (pin "2") (pinfunction "2_2") (pintype "passive"))
    )
    (net (code "55") (name "D53") (class "Default")
      (node (ref "D161") (pin "A") (pinfunction "A_A") (pintype "passive"))
      (node (ref "D162") (pin "C") (pinfunction "C_C") (pintype "passive"))
      (node (ref "J5") (pin "54") (pinfunction "54_54") (pintype "bidirectional"))
      (node (ref "R54") (pin "2") (pinfunction "2_2") (pintype "passive"))
    )
    (net (code "56") (name "D54") (class "Default")
      (node (ref "D164") (pin "A") (pinfunction "A_A") (pintype "passive"))
      (node (ref "D165") (pin "C") (pinfunction "C_C") (pintype "passive"))
      (node (ref "J5") (pin "55") (pinfunction "55_55") (pintype "bidirectional"))
      (node (ref "R55") (pin "2") (pinfunction "2_2") (pintype "passive"))
    )
    (net (code "57") (name "D55") (class "Default")
      (node (ref "D167") (pin "A") (pinfunction "A_A") (pintype "passive"))
      (node (ref "D168") (pin "C") (pinfunction "C_C") (pintype "passive"))
      (node (ref "J5") (pin "56") (pinfunction "56_56") (pintype "bidirectional"))
      (node (ref "R56") (pin "2") (pinfunction "2_2") (pintype "passive"))
    )
    (net (code "58") (name "D56") (class "Default")
      (node (ref "D170") (pin "A") (pinfunction "A_A") (pintype "passive"))
      (node (ref "D171") (pin "C") (pinfunction "C_C") (pintype "passive"))
      (node (ref "J5") (pin "57") (pinfunction "57_57") (pintype "bidirectional"))
      (node (ref "R57") (pin "2") (pinfunction "2_2") (pintype "passive"))
    )
    (net (code "59") (name "D57") (class "Default")
      (node (ref "D173") (pin "A") (pinfunction "A_A") (pintype "passive"))
      (node (ref "D174") (pin "C") (pinfunction "C_C") (pintype "passive"))
      (node (ref "J5") (pin "58") (pinfunction "58_58") (pintype "bidirectional"))
      (node (ref "R58") (pin "2") (pinfunction "2_2") (pintype "passive"))
    )
    (net (code "60") (name "D58") (class "Default")
      (node (ref "D176") (pin "A") (pinfunction "A_A") (pintype "passive"))
      (node (ref "D177") (pin "C") (pinfunction "C_C") (pintype "passive"))
      (node (ref "J5") (pin "59") (pinfunction "59_59") (pintype "bidirectional"))
      (node (ref "R59") (pin "2") (pinfunction "2_2") (pintype "passive"))
    )
    (net (code "61") (name "D59") (class "Default")
      (node (ref "D179") (pin "A") (pinfunction "A_A") (pintype "passive"))
      (node (ref "D180") (pin "C") (pinfunction "C_C") (pintype "passive"))
      (node (ref "J5") (pin "60") (pinfunction "60_60") (pintype "bidirectional"))
      (node (ref "R60") (pin "2") (pinfunction "2_2") (pintype "passive"))
    )
    (net (code "62") (name "D60") (class "Default")
      (node (ref "D182") (pin "A") (pinfunction "A_A") (pintype "passive"))
      (node (ref "D183") (pin "C") (pinfunction "C_C") (pintype "passive"))
      (node (ref "J5") (pin "61") (pinfunction "61_61") (pintype "bidirectional"))
      (node (ref "R61") (pin "2") (pinfunction "2_2") (pintype "passive"))
    )
    (net (code "63") (name "D61") (class "Default")
      (node (ref "D185") (pin "A") (pinfunction "A_A") (pintype "passive"))
      (node (ref "D186") (pin "C") (pinfunction "C_C") (pintype "passive"))
      (node (ref "J5") (pin "62") (pinfunction "62_62") (pintype "bidirectional"))
      (node (ref "R62") (pin "2") (pinfunction "2_2") (pintype "passive"))
    )
    (net (code "64") (name "D62") (class "Default")
      (node (ref "D188") (pin "A") (pinfunction "A_A") (pintype "passive"))
      (node (ref "D189") (pin "C") (pinfunction "C_C") (pintype "passive"))
      (node (ref "J5") (pin "63") (pinfunction "63_63") (pintype "bidirectional"))
      (node (ref "R63") (pin "2") (pinfunction "2_2") (pintype "passive"))
    )
    (net (code "65") (name "D63") (class "Default")
      (node (ref "D191") (pin "A") (pinfunction "A_A") (pintype "passive"))
      (node (ref "D192") (pin "C") (pinfunction "C_C") (pintype "passive"))
      (node (ref "J5") (pin "64") (pinfunction "64_64") (pintype "bidirectional"))
      (node (ref "R64") (pin "2") (pinfunction "2_2") (pintype "passive"))
    )
    (net (code "66") (name "DIN_0") (class "Default")
      (node (ref "J1") (pin "2") (pinfunction "2_2") (pintype "bidirectional"))
      (node (ref "R1") (pin "1") (pinfunction "1_1") (pintype "passive"))
    )
    (net (code "67") (name "DIN_1") (class "Default")
      (node (ref "J1") (pin "3") (pinfunction "3_3") (pintype "bidirectional"))
      (node (ref "R2") (pin "1") (pinfunction "1_1") (pintype "passive"))
    )
    (net (code "68") (name "DIN_2") (class "Default")
      (node (ref "J1") (pin "4") (pinfunction "4_4") (pintype "bidirectional"))
      (node (ref "R3") (pin "1") (pinfunction "1_1") (pintype "passive"))
    )
    (net (code "69") (name "DIN_3") (class "Default")
      (node (ref "J1") (pin "5") (pinfunction "5_5") (pintype "bidirectional"))
      (node (ref "R4") (pin "1") (pinfunction "1_1") (pintype "passive"))
    )
    (net (code "70") (name "DIN_4") (class "Default")
      (node (ref "J1") (pin "6") (pinfunction "6_6") (pintype "bidirectional"))
      (node (ref "R5") (pin "1") (pinfunction "1_1") (pintype "passive"))
    )
    (net (code "71") (name "DIN_5") (class "Default")
      (node (ref "J1") (pin "7") (pinfunction "7_7") (pintype "bidirectional"))
      (node (ref "R6") (pin "1") (pinfunction "1_1") (pintype "passive"))
    )
    (net (code "72") (name "DIN_6") (class "Default")
      (node (ref "J1") (pin "8") (pinfunction "8_8") (pintype "bidirectional"))
      (node (ref "R7") (pin "1") (pinfunction "1_1") (pintype "passive"))
    )
    (net (code "73") (name "DIN_7") (class "Default")
      (node (ref "J1") (pin "9") (pinfunction "9_9") (pintype "bidirectional"))
      (node (ref "R8") (pin "1") (pinfunction "1_1") (pintype "passive"))
    )
    (net (code "74") (name "DIN_8") (class "Default")
      (node (ref "J1") (pin "12") (pinfunction "12_12") (pintype "bidirectional"))
      (node (ref "R9") (pin "1") (pinfunction "1_1") (pintype "passive"))
    )
    (net (code "75") (name "DIN_9") (class "Default")
      (node (ref "J1") (pin "13") (pinfunction "13_13") (pintype "bidirectional"))
      (node (ref "R10") (pin "1") (pinfunction "1_1") (pintype "passive"))
    )
    (net (code "76") (name "DIN_10") (class "Default")
      (node (ref "J1") (pin "14") (pinfunction "14_14") (pintype "bidirectional"))
      (node (ref "R11") (pin "1") (pinfunction "1_1") (pintype "passive"))
    )
    (net (code "77") (name "DIN_11") (class "Default")
      (node (ref "J1") (pin "15") (pinfunction "15_15") (pintype "bidirectional"))
      (node (ref "R12") (pin "1") (pinfunction "1_1") (pintype "passive"))
    )
    (net (code "78") (name "DIN_12") (class "Default")
      (node (ref "J1") (pin "16") (pinfunction "16_16") (pintype "bidirectional"))
      (node (ref "R13") (pin "1") (pinfunction "1_1") (pintype "passive"))
    )
    (net (code "79") (name "DIN_13") (class "Default")
      (node (ref "J1") (pin "17") (pinfunction "17_17") (pintype "bidirectional"))
      (node (ref "R14") (pin "1") (pinfunction "1_1") (pintype "passive"))
    )
    (net (code "80") (name "DIN_14") (class "Default")
      (node (ref "J1") (pin "18") (pinfunction "18_18") (pintype "bidirectional"))
      (node (ref "R15") (pin "1") (pinfunction "1_1") (pintype "passive"))
    )
    (net (code "81") (name "DIN_15") (class "Default")
      (node (ref "J1") (pin "19") (pinfunction "19_19") (pintype "bidirectional"))
      (node (ref "R16") (pin "1") (pinfunction "1_1") (pintype "passive"))
    )
    (net (code "82") (name "DIN_16") (class "Default")
      (node (ref "J2") (pin "2") (pinfunction "2_2") (pintype "bidirectional"))
      (node (ref "R17") (pin "1") (pinfunction "1_1") (pintype "passive"))
    )
    (net (code "83") (name "DIN_17") (class "Default")
      (node (ref "J2") (pin "3") (pinfunction "3_3") (pintype "bidirectional"))
      (node (ref "R18") (pin "1") (pinfunction "1_1") (pintype "passive"))
    )
    (net (code "84") (name "DIN_18") (class "Default")
      (node (ref "J2") (pin "4") (pinfunction "4_4") (pintype "bidirectional"))
      (node (ref "R19") (pin "1") (pinfunction "1_1") (pintype "passive"))
    )
    (net (code "85") (name "DIN_19") (class "Default")
      (node (ref "J2") (pin "5") (pinfunction "5_5") (pintype "bidirectional"))
      (node (ref "R20") (pin "1") (pinfunction "1_1") (pintype "passive"))
    )
    (net (code "86") (name "DIN_20") (class "Default")
      (node (ref "J2") (pin "6") (pinfunction "6_6") (pintype "bidirectional"))
      (node (ref "R21") (pin "1") (pinfunction "1_1") (pintype "passive"))
    )
    (net (code "87") (name "DIN_21") (class "Default")
      (node (ref "J2") (pin "7") (pinfunction "7_7") (pintype "bidirectional"))
      (node (ref "R22") (pin "1") (pinfunction "1_1") (pintype "passive"))
    )
    (net (code "88") (name "DIN_22") (class "Default")
      (node (ref "J2") (pin "8") (pinfunction "8_8") (pintype "bidirectional"))
      (node (ref "R23") (pin "1") (pinfunction "1_1") (pintype "passive"))
    )
    (net (code "89") (name "DIN_23") (class "Default")
      (node (ref "J2") (pin "9") (pinfunction "9_9") (pintype "bidirectional"))
      (node (ref "R24") (pin "1") (pinfunction "1_1") (pintype "passive"))
    )
    (net (code "90") (name "DIN_24") (class "Default")
      (node (ref "J2") (pin "12") (pinfunction "12_12") (pintype "bidirectional"))
      (node (ref "R25") (pin "1") (pinfunction "1_1") (pintype "passive"))
    )
    (net (code "91") (name "DIN_25") (class "Default")
      (node (ref "J2") (pin "13") (pinfunction "13_13") (pintype "bidirectional"))
      (node (ref "R26") (pin "1") (pinfunction "1_1") (pintype "passive"))
    )
    (net (code "92") (name "DIN_26") (class "Default")
      (node (ref "J2") (pin "14") (pinfunction "14_14") (pintype "bidirectional"))
      (node (ref "R27") (pin "1") (pinfunction "1_1") (pintype "passive"))
    )
    (net (code "93") (name "DIN_27") (class "Default")
      (node (ref "J2") (pin "15") (pinfunction "15_15") (pintype "bidirectional"))
      (node (ref "R28") (pin "1") (pinfunction "1_1") (pintype "passive"))
    )
    (net (code "94") (name "DIN_28") (class "Default")
      (node (ref "J2") (pin "16") (pinfunction "16_16") (pintype "bidirectional"))
      (node (ref "R29") (pin "1") (pinfunction "1_1") (pintype "passive"))
    )
    (net (code "95") (name "DIN_29") (class "Default")
      (node (ref "J2") (pin "17") (pinfunction "17_17") (pintype "bidirectional"))
      (node (ref "R30") (pin "1") (pinfunction "1_1") (pintype "passive"))
    )
    (net (code "96") (name "DIN_30") (class "Default")
      (node (ref "J2") (pin "18") (pinfunction "18_18") (pintype "bidirectional"))
      (node (ref "R31") (pin "1") (pinfunction "1_1") (pintype "passive"))
    )
    (net (code "97") (name "DIN_31") (class "Default")
      (node (ref "J2") (pin "19") (pinfunction "19_19") (pintype "bidirectional"))
      (node (ref "R32") (pin "1") (pinfunction "1_1") (pintype "passive"))
    )
    (net (code "98") (name "DIN_32") (class "Default")
      (node (ref "J3") (pin "2") (pinfunction "2_2") (pintype "bidirectional"))
      (node (ref "R33") (pin "1") (pinfunction "1_1") (pintype "passive"))
    )
    (net (code "99") (name "DIN_33") (class "Default")
      (node (ref "J3") (pin "3") (pinfunction "3_3") (pintype "bidirectional"))
      (node (ref "R34") (pin "1") (pinfunction "1_1") (pintype "passive"))
    )
    (net (code "100") (name "DIN_34") (class "Default")
      (node (ref "J3") (pin "4") (pinfunction "4_4") (pintype "bidirectional"))
      (node (ref "R35") (pin "1") (pinfunction "1_1") (pintype "passive"))
    )
    (net (code "101") (name "DIN_35") (class "Default")
      (node (ref "J3") (pin "5") (pinfunction "5_5") (pintype "bidirectional"))
      (node (ref "R36") (pin "1") (pinfunction "1_1") (pintype "passive"))
    )
    (net (code "102") (name "DIN_36") (class "Default")
      (node (ref "J3") (pin "6") (pinfunction "6_6") (pintype "bidirectional"))
      (node (ref "R37") (pin "1") (pinfunction "1_1") (pintype "passive"))
    )
    (net (code "103") (name "DIN_37") (class "Default")
      (node (ref "J3") (pin "7") (pinfunction "7_7") (pintype "bidirectional"))
      (node (ref "R38") (pin "1") (pinfunction "1_1") (pintype "passive"))
    )
    (net (code "104") (name "DIN_38") (class "Default")
      (node (ref "J3") (pin "8") (pinfunction "8_8") (pintype "bidirectional"))
      (node (ref "R39") (pin "1") (pinfunction "1_1") (pintype "passive"))
    )
    (net (code "105") (name "DIN_39") (class "Default")
      (node (ref "J3") (pin "9") (pinfunction "9_9") (pintype "bidirectional"))
      (node (ref "R40") (pin "1") (pinfunction "1_1") (pintype "passive"))
    )
    (net (code "106") (name "DIN_40") (class "Default")
      (node (ref "J3") (pin "12") (pinfunction "12_12") (pintype "bidirectional"))
      (node (ref "R41") (pin "1") (pinfunction "1_1") (pintype "passive"))
    )
    (net (code "107") (name "DIN_41") (class "Default")
      (node (ref "J3") (pin "13") (pinfunction "13_13") (pintype "bidirectional"))
      (node (ref "R42") (pin "1") (pinfunction "1_1") (pintype "passive"))
    )
    (net (code "108") (name "DIN_42") (class "Default")
      (node (ref "J3") (pin "14") (pinfunction "14_14") (pintype "bidirectional"))
      (node (ref "R43") (pin "1") (pinfunction "1_1") (pintype "passive"))
    )
    (net (code "109") (name "DIN_43") (class "Default")
      (node (ref "J3") (pin "15") (pinfunction "15_15") (pintype "bidirectional"))
      (node (ref "R44") (pin "1") (pinfunction "1_1") (pintype "passive"))
    )
    (net (code "110") (name "DIN_44") (class "Default")
      (node (ref "J3") (pin "16") (pinfunction "16_16") (pintype "bidirectional"))
      (node (ref "R45") (pin "1") (pinfunction "1_1") (pintype "passive"))
    )
    (net (code "111") (name "DIN_45") (class "Default")
      (node (ref "J3") (pin "17") (pinfunction "17_17") (pintype "bidirectional"))
      (node (ref "R46") (pin "1") (pinfunction "1_1") (pintype "passive"))
    )
    (net (code "112") (name "DIN_46") (class "Default")
      (node (ref "J3") (pin "18") (pinfunction "18_18") (pintype "bidirectional"))
      (node (ref "R47") (pin "1") (pinfunction "1_1") (pintype "passive"))
    )
    (net (code "113") (name "DIN_47") (class "Default")
      (node (ref "J3") (pin "19") (pinfunction "19_19") (pintype "bidirectional"))
      (node (ref "R48") (pin "1") (pinfunction "1_1") (pintype "passive"))
    )
    (net (code "114") (name "DIN_48") (class "Default")
      (node (ref "J4") (pin "2") (pinfunction "2_2") (pintype "bidirectional"))
      (node (ref "R49") (pin "1") (pinfunction "1_1") (pintype "passive"))
    )
    (net (code "115") (name "DIN_49") (class "Default")
      (node (ref "J4") (pin "3") (pinfunction "3_3") (pintype "bidirectional"))
      (node (ref "R50") (pin "1") (pinfunction "1_1") (pintype "passive"))
    )
    (net (code "116") (name "DIN_50") (class "Default")
      (node (ref "J4") (pin "4") (pinfunction "4_4") (pintype "bidirectional"))
      (node (ref "R51") (pin "1") (pinfunction "1_1") (pintype "passive"))
    )
    (net (code "117") (name "DIN_51") (class "Default")
      (node (ref "J4") (pin "5") (pinfunction "5_5") (pintype "bidirectional"))
      (node (ref "R52") (pin "1") (pinfunction "1_1") (pintype "passive"))
    )
    (net (code "118") (name "DIN_52") (class "Default")
      (node (ref "J4") (pin "6") (pinfunction "6_6") (pintype "bidirectional"))
      (node (ref "R53") (pin "1") (pinfunction "1_1") (pintype "passive"))
    )
    (net (code "119") (name "DIN_53") (class "Default")
      (node (ref "J4") (pin "7") (pinfunction "7_7") (pintype "bidirectional"))
      (node (ref "R54") (pin "1") (pinfunction "1_1") (pintype "passive"))
    )
    (net (code "120") (name "DIN_54") (class "Default")
      (node (ref "J4") (pin "8") (pinfunction "8_8") (pintype "bidirectional"))
      (node (ref "R55") (pin "1") (pinfunction "1_1") (pintype "passive"))
    )
    (net (code "121") (name "DIN_55") (class "Default")
      (node (ref "J4") (pin "9") (pinfunction "9_9") (pintype "bidirectional"))
      (node (ref "R56") (pin "1") (pinfunction "1_1") (pintype "passive"))
    )
    (net (code "122") (name "DIN_56") (class "Default")
      (node (ref "J4") (pin "12") (pinfunction "12_12") (pintype "bidirectional"))
      (node (ref "R57") (pin "1") (pinfunction "1_1") (pintype "passive"))
    )
    (net (code "123") (name "DIN_57") (class "Default")
      (node (ref "J4") (pin "13") (pinfunction "13_13") (pintype "bidirectional"))
      (node (ref "R58") (pin "1") (pinfunction "1_1") (pintype "passive"))
    )
    (net (code "124") (name "DIN_58") (class "Default")
      (node (ref "J4") (pin "14") (pinfunction "14_14") (pintype "bidirectional"))
      (node (ref "R59") (pin "1") (pinfunction "1_1") (pintype "passive"))
    )
    (net (code "125") (name "DIN_59") (class "Default")
      (node (ref "J4") (pin "15") (pinfunction "15_15") (pintype "bidirectional"))
      (node (ref "R60") (pin "1") (pinfunction "1_1") (pintype "passive"))
    )
    (net (code "126") (name "DIN_60") (class "Default")
      (node (ref "J4") (pin "16") (pinfunction "16_16") (pintype "bidirectional"))
      (node (ref "R61") (pin "1") (pinfunction "1_1") (pintype "passive"))
    )
    (net (code "127") (name "DIN_61") (class "Default")
      (node (ref "J4") (pin "17") (pinfunction "17_17") (pintype "bidirectional"))
      (node (ref "R62") (pin "1") (pinfunction "1_1") (pintype "passive"))
    )
    (net (code "128") (name "DIN_62") (class "Default")
      (node (ref "J4") (pin "18") (pinfunction "18_18") (pintype "bidirectional"))
      (node (ref "R63") (pin "1") (pinfunction "1_1") (pintype "passive"))
    )
    (net (code "129") (name "DIN_63") (class "Default")
      (node (ref "J4") (pin "19") (pinfunction "19_19") (pintype "bidirectional"))
      (node (ref "R64") (pin "1") (pinfunction "1_1") (pintype "passive"))
    )
    (net (code "130") (name "GND") (class "Default")
      (node (ref "C1") (pin "2") (pinfunction "2_2") (pintype "passive"))
      (node (ref "C2") (pin "1") (pinfunction "1_1") (pintype "passive"))
      (node (ref "C3") (pin "1") (pinfunction "1_1") (pintype "passive"))
      (node (ref "C4") (pin "1") (pinfunction "1_1") (pintype "passive"))
      (node (ref "D102") (pin "A") (pinfunction "A_A") (pintype "passive"))
      (node (ref "D105") (pin "A") (pinfunction "A_A") (pintype "passive"))
      (node (ref "D108") (pin "A") (pinfunction "A_A") (pintype "passive"))
      (node (ref "D111") (pin "A") (pinfunction "A_A") (pintype "passive"))
      (node (ref "D114") (pin "A") (pinfunction "A_A") (pintype "passive"))
      (node (ref "D117") (pin "A") (pinfunction "A_A") (pintype "passive"))
      (node (ref "D12") (pin "A") (pinfunction "A_A") (pintype "passive"))
      (node (ref "D120") (pin "A") (pinfunction "A_A") (pintype "passive"))
      (node (ref "D123") (pin "A") (pinfunction "A_A") (pintype "passive"))
      (node (ref "D126") (pin "A") (pinfunction "A_A") (pintype "passive"))
      (node (ref "D129") (pin "A") (pinfunction "A_A") (pintype "passive"))
      (node (ref "D132") (pin "A") (pinfunction "A_A") (pintype "passive"))
      (node (ref "D135") (pin "A") (pinfunction "A_A") (pintype "passive"))
      (node (ref "D138") (pin "A") (pinfunction "A_A") (pintype "passive"))
      (node (ref "D141") (pin "A") (pinfunction "A_A") (pintype "passive"))
      (node (ref "D144") (pin "A") (pinfunction "A_A") (pintype "passive"))
      (node (ref "D147") (pin "A") (pinfunction "A_A") (pintype "passive"))
      (node (ref "D15") (pin "A") (pinfunction "A_A") (pintype "passive"))
      (node (ref "D150") (pin "A") (pinfunction "A_A") (pintype "passive"))
      (node (ref "D153") (pin "A") (pinfunction "A_A") (pintype "passive"))
      (node (ref "D156") (pin "A") (pinfunction "A_A") (pintype "passive"))
      (node (ref "D159") (pin "A") (pinfunction "A_A") (pintype "passive"))
      (node (ref "D162") (pin "A") (pinfunction "A_A") (pintype "passive"))
      (node (ref "D165") (pin "A") (pinfunction "A_A") (pintype "passive"))
      (node (ref "D168") (pin "A") (pinfunction "A_A") (pintype "passive"))
      (node (ref "D171") (pin "A") (pinfunction "A_A") (pintype "passive"))
      (node (ref "D174") (pin "A") (pinfunction "A_A") (pintype "passive"))
      (node (ref "D177") (pin "A") (pinfunction "A_A") (pintype "passive"))
      (node (ref "D18") (pin "A") (pinfunction "A_A") (pintype "passive"))
      (node (ref "D180") (pin "A") (pinfunction "A_A") (pintype "passive"))
      (node (ref "D183") (pin "A") (pinfunction "A_A") (pintype "passive"))
      (node (ref "D186") (pin "A") (pinfunction "A_A") (pintype "passive"))
      (node (ref "D189") (pin "A") (pinfunction "A_A") (pintype "passive"))
      (node (ref "D192") (pin "A") (pinfunction "A_A") (pintype "passive"))
      (node (ref "D21") (pin "A") (pinfunction "A_A") (pintype "passive"))
      (node (ref "D24") (pin "A") (pinfunction "A_A") (pintype "passive"))
      (node (ref "D27") (pin "A") (pinfunction "A_A") (pintype "passive"))
      (node (ref "D3") (pin "A") (pinfunction "A_A") (pintype "passive"))
      (node (ref "D30") (pin "A") (pinfunction "A_A") (pintype "passive"))
      (node (ref "D33") (pin "A") (pinfunction "A_A") (pintype "passive"))
      (node (ref "D36") (pin "A") (pinfunction "A_A") (pintype "passive"))
      (node (ref "D39") (pin "A") (pinfunction "A_A") (pintype "passive"))
      (node (ref "D42") (pin "A") (pinfunction "A_A") (pintype "passive"))
      (node (ref "D45") (pin "A") (pinfunction "A_A") (pintype "passive"))
      (node (ref "D48") (pin "A") (pinfunction "A_A") (pintype "passive"))
      (node (ref "D51") (pin "A") (pinfunction "A_A") (pintype "passive"))
      (node (ref "D54") (pin "A") (pinfunction "A_A") (pintype "passive"))
      (node (ref "D57") (pin "A") (pinfunction "A_A") (pintype "passive"))
      (node (ref "D6") (pin "A") (pinfunction "A_A") (pintype "passive"))
      (node (ref "D60") (pin "A") (pinfunction "A_A") (pintype "passive"))
      (node (ref "D63") (pin "A") (pinfunction "A_A") (pintype "passive"))
      (node (ref "D66") (pin "A") (pinfunction "A_A") (pintype "passive"))
      (node (ref "D69") (pin "A") (pinfunction "A_A") (pintype "passive"))
      (node (ref "D72") (pin "A") (pinfunction "A_A") (pintype "passive"))
      (node (ref "D75") (pin "A") (pinfunction "A_A") (pintype "passive"))
      (node (ref "D78") (pin "A") (pinfunction "A_A") (pintype "passive"))
      (node (ref "D81") (pin "A") (pinfunction "A_A") (pintype "passive"))
      (node (ref "D84") (pin "A") (pinfunction "A_A") (pintype "passive"))
      (node (ref "D87") (pin "A") (pinfunction "A_A") (pintype "passive"))
      (node (ref "D9") (pin "A") (pinfunction "A_A") (pintype "passive"))
      (node (ref "D90") (pin "A") (pinfunction "A_A") (pintype "passive"))
      (node (ref "D93") (pin "A") (pinfunction "A_A") (pintype "passive"))
      (node (ref "D96") (pin "A") (pinfunction "A_A") (pintype "passive"))
      (node (ref "D99") (pin "A") (pinfunction "A_A") (pintype "passive"))
      (node (ref "J1") (pin "1") (pinfunction "1_1") (pintype "bidirectional"))
      (node (ref "J1") (pin "10") (pinfunction "10_10") (pintype "bidirectional"))
      (node (ref "J1") (pin "11") (pinfunction "11_11") (pintype "bidirectional"))
      (node (ref "J1") (pin "20") (pinfunction "20_20") (pintype "bidirectional"))
      (node (ref "J2") (pin "1") (pinfunction "1_1") (pintype "bidirectional"))
      (node (ref "J2") (pin "10") (pinfunction "10_10") (pintype "bidirectional"))
      (node (ref "J2") (pin "11") (pinfunction "11_11") (pintype "bidirectional"))
      (node (ref "J2") (pin "20") (pinfunction "20_20") (pintype "bidirectional"))
      (node (ref "J3") (pin "1") (pinfunction "1_1") (pintype "bidirectional"))
      (node (ref "J3") (pin "10") (pinfunction "10_10") (pintype "bidirectional"))
      (node (ref "J3") (pin "11") (pinfunction "11_11") (pintype "bidirectional"))
      (node (ref "J3") (pin "20") (pinfunction "20_20") (pintype "bidirectional"))
      (node (ref "J4") (pin "1") (pinfunction "1_1") (pintype "bidirectional"))
      (node (ref "J4") (pin "10") (pinfunction "10_10") (pintype "bidirectional"))
      (node (ref "J4") (pin "11") (pinfunction "11_11") (pintype "bidirectional"))
      (node (ref "J4") (pin "20") (pinfunction "20_20") (pintype "bidirectional"))
      (node (ref "PP4") (pin "1") (pinfunction "P$1_1") (pintype "bidirectional"))
      (node (ref "PP5") (pin "1") (pinfunction "P$1_1") (pintype "bidirectional"))
      (node (ref "PP6") (pin "1") (pinfunction "P$1_1") (pintype "bidirectional"))
      (node (ref "R65") (pin "1") (pinfunction "1_1") (pintype "passive"))
    )
  )
)
